# Carrier.net
KiCad netlist of a schematic drawn in Altium Designer
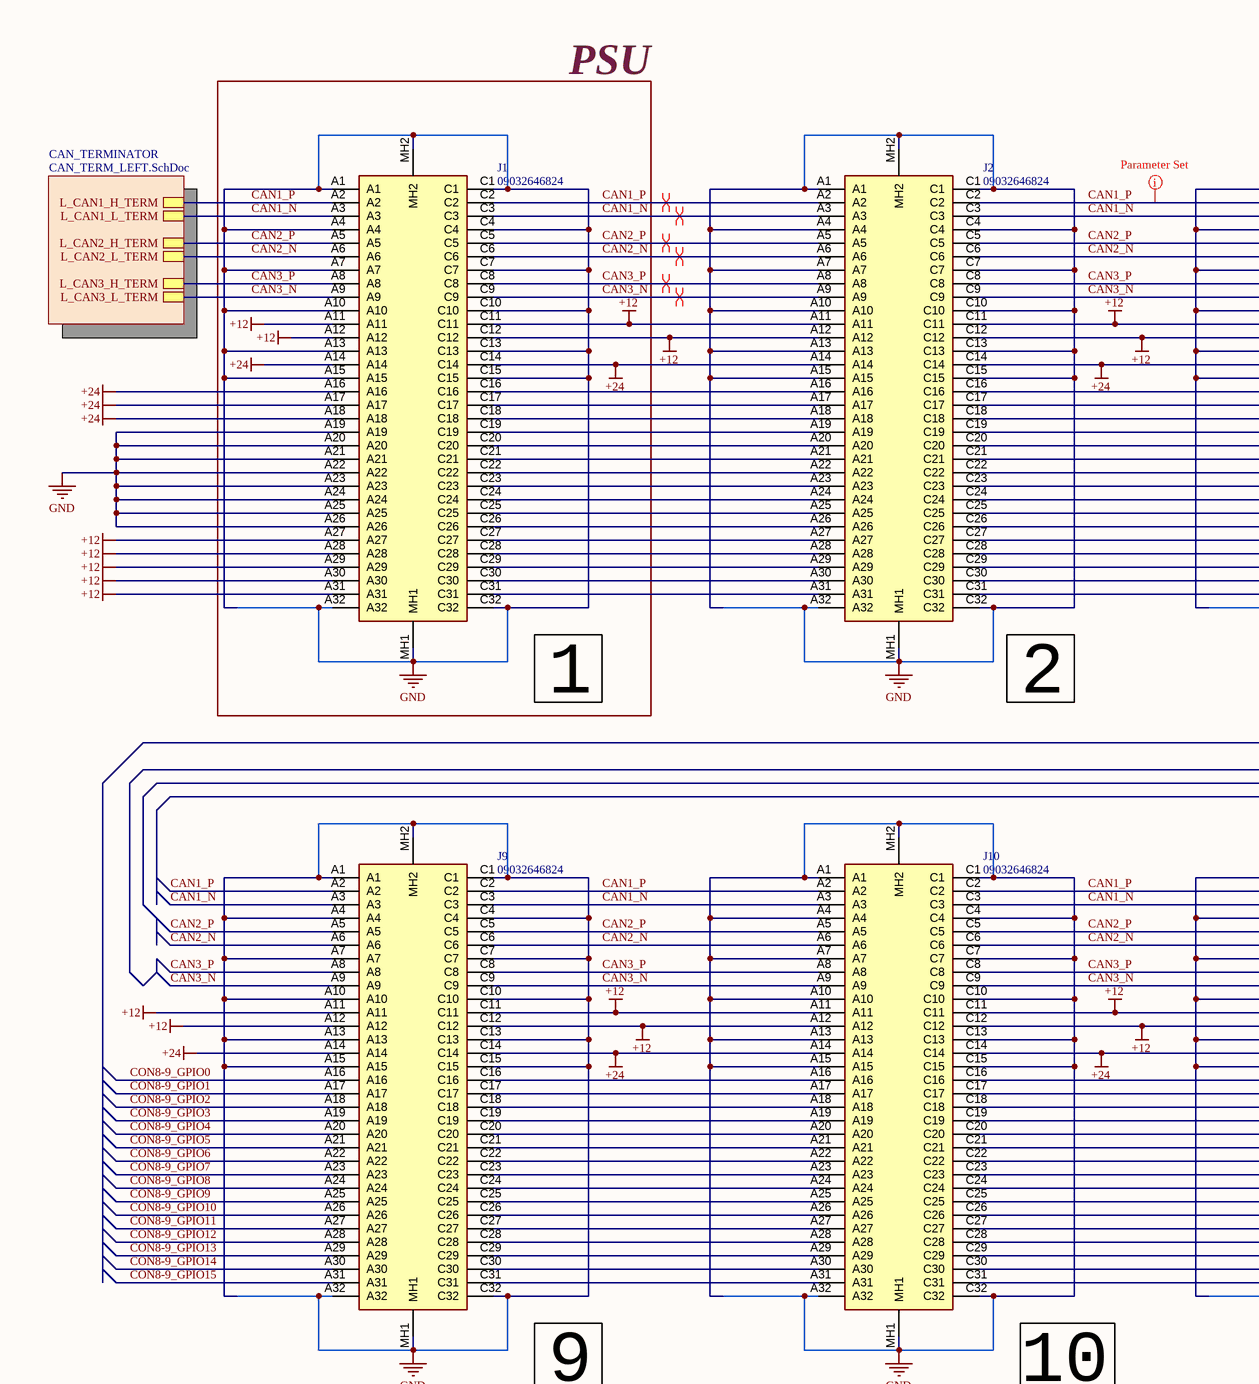
[diagram p0: Carrier.SchDoc, top left]
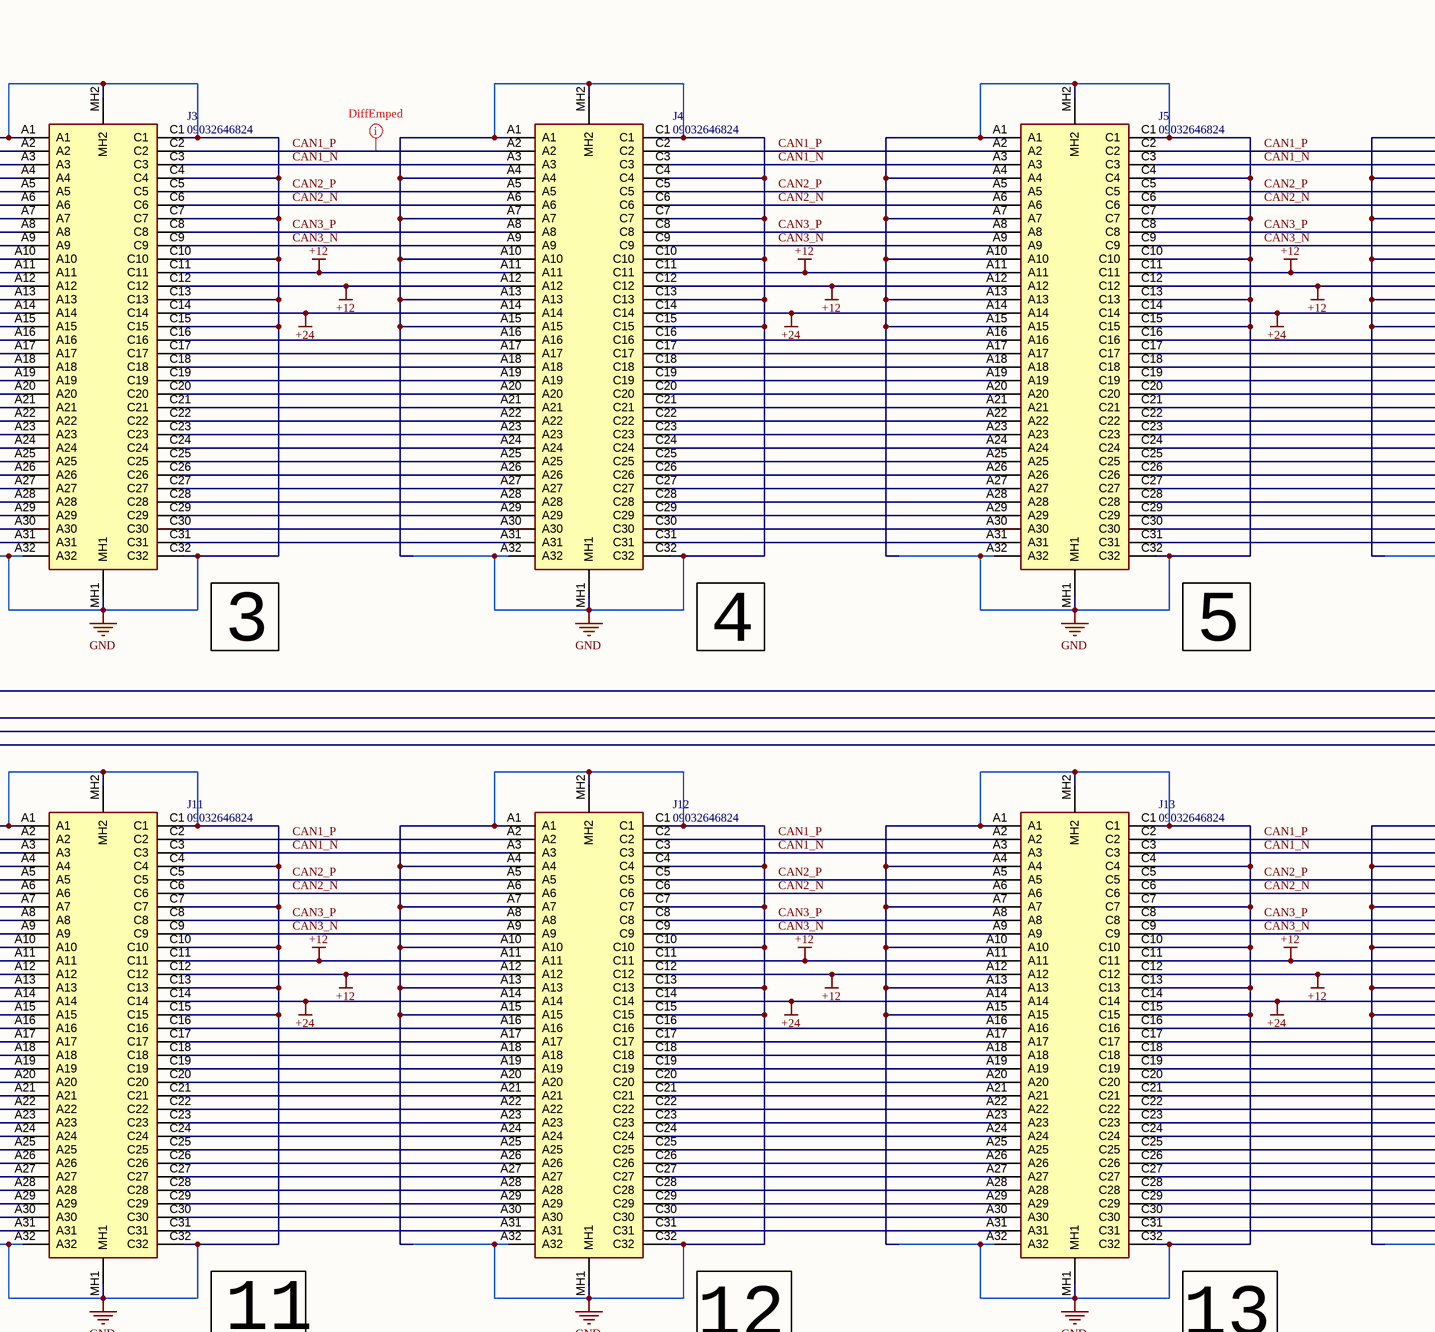
[diagram p1: Carrier.SchDoc, top middle]
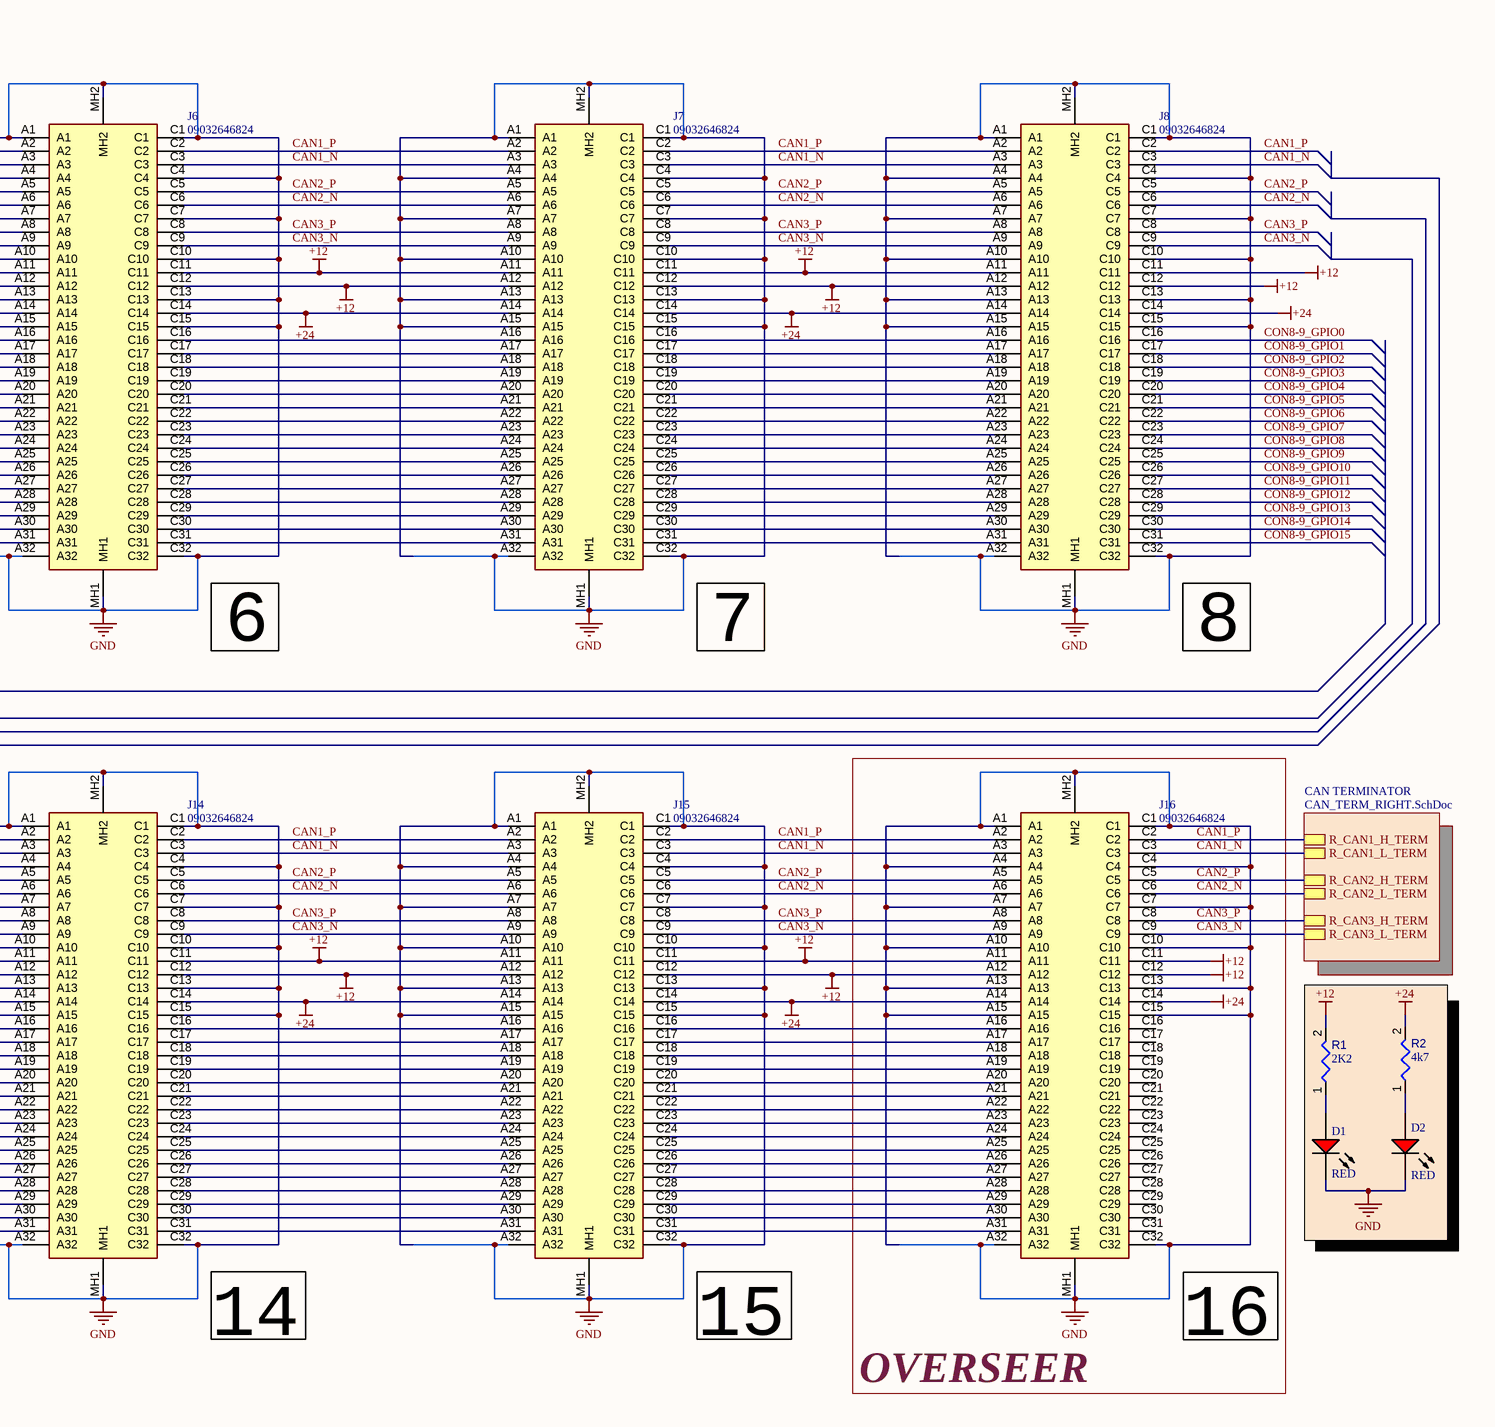
[diagram p2: Carrier.SchDoc, top right]
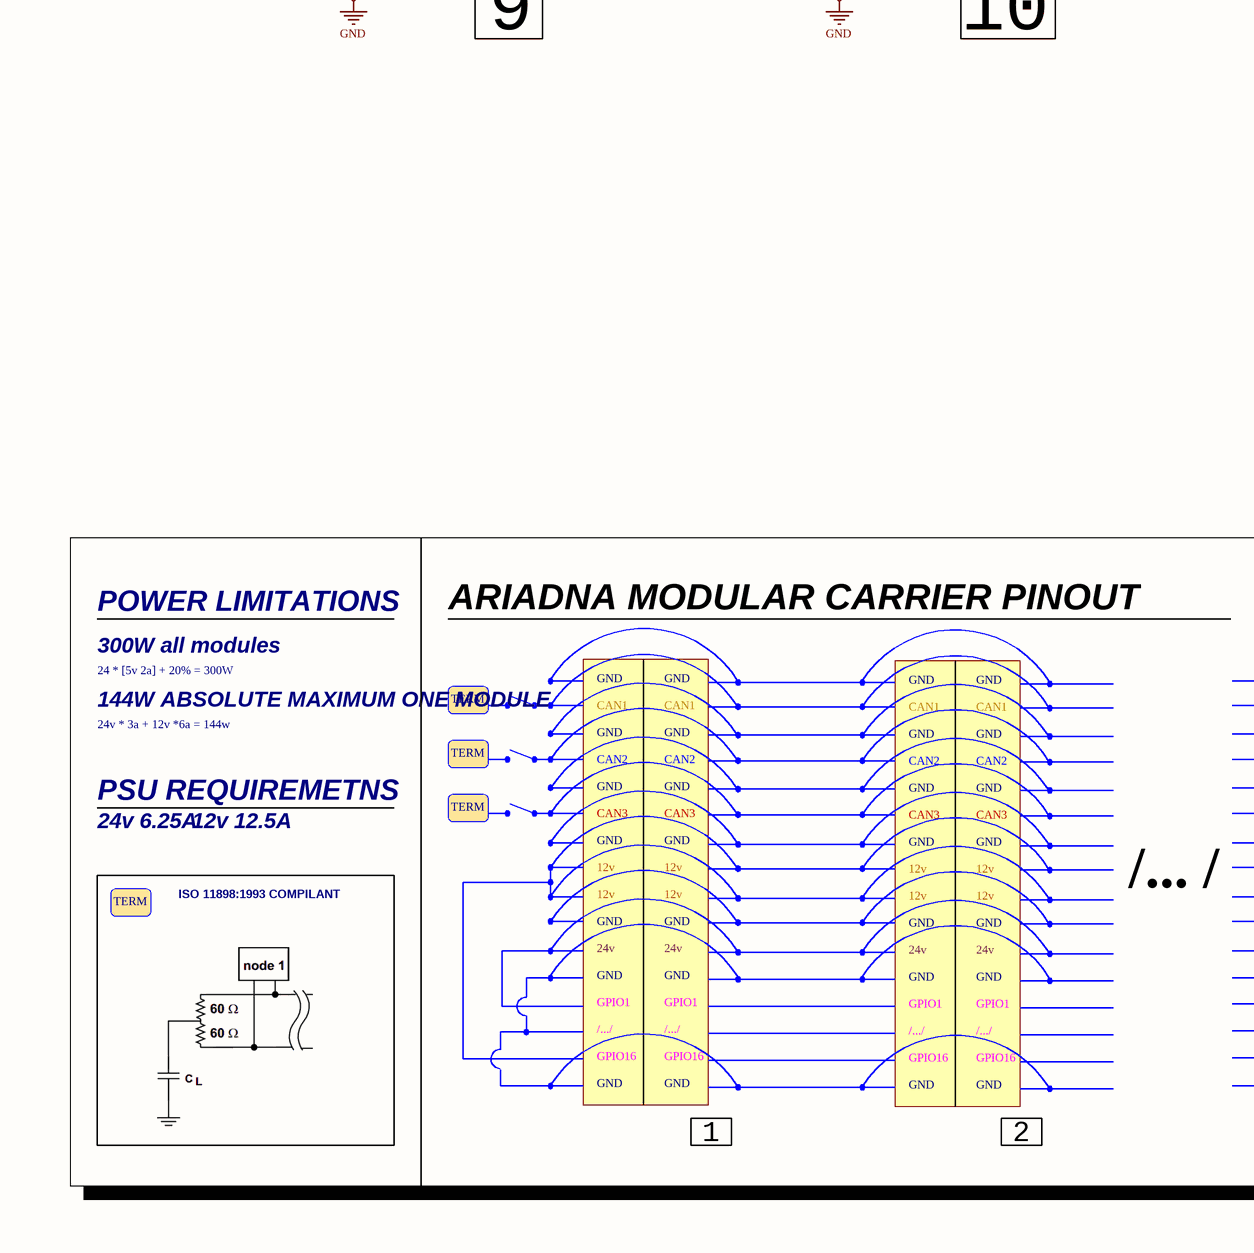
[diagram p3: Carrier.SchDoc, bottom left]
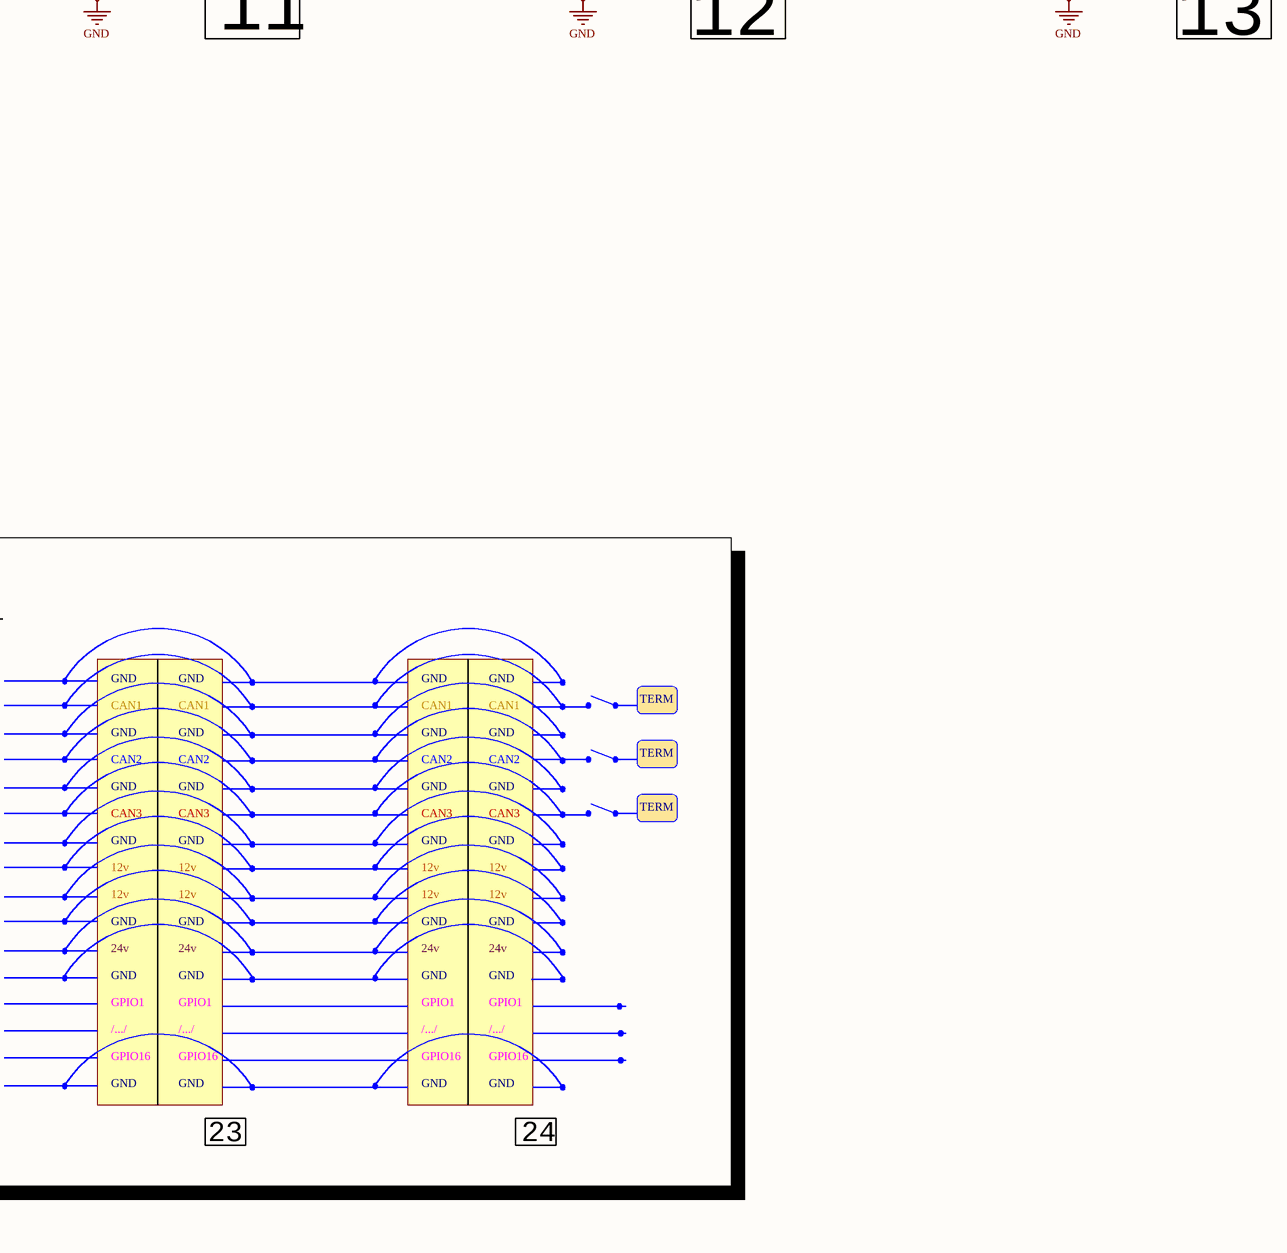
[diagram p4: Carrier.SchDoc, bottom middle]
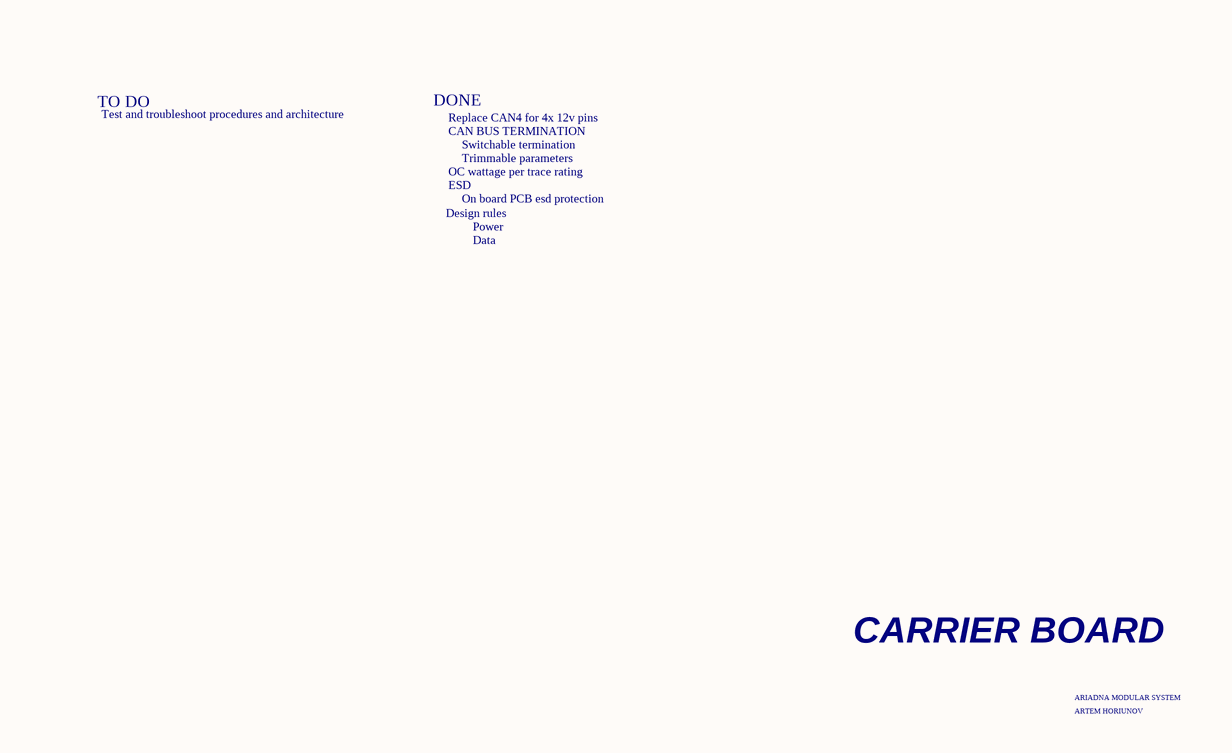
[diagram p5: Carrier.SchDoc, bottom right]

(export (version "E")
  (design (tool "Eeschema 10.0.6"))
  (components
    (comp (ref "D1")
      (value "RED")
      (footprint "AVAG-HSMX-C190_V")
      (description "LED Uni-Color Red, 65 mW, 20 mA, -40 to 85 degC, 2-Pin SMD, RoHS, Tape and Reel")
      (libsource (lib "Altium Content Vault") (part "LED-RED-AK-2"))
    )
    (comp (ref "D2")
      (value "RED")
      (footprint "AVAG-HSMX-C190_V")
      (description "LED Uni-Color Red, 65 mW, 20 mA, -40 to 85 degC, 2-Pin SMD, RoHS, Tape and Reel")
      (libsource (lib "Altium Content Vault") (part "LED-RED-AK-2"))
    )
    (comp (ref "J1")
      (value "09032646824")
      (footprint "09032646824")
      (description "DIN C female straight 64pin, 2.9mm tails, PL2 (rows a,c loaded)")
      (libsource (lib "09032646824") (part "09032646824"))
    )
    (comp (ref "J2")
      (value "09032646824")
      (footprint "09032646824")
      (description "DIN C female straight 64pin, 2.9mm tails, PL2 (rows a,c loaded)")
      (libsource (lib "09032646824") (part "09032646824"))
    )
    (comp (ref "J3")
      (value "09032646824")
      (footprint "09032646824")
      (description "DIN C female straight 64pin, 2.9mm tails, PL2 (rows a,c loaded)")
      (libsource (lib "09032646824") (part "09032646824"))
    )
    (comp (ref "J4")
      (value "09032646824")
      (footprint "09032646824")
      (description "DIN C female straight 64pin, 2.9mm tails, PL2 (rows a,c loaded)")
      (libsource (lib "09032646824") (part "09032646824"))
    )
    (comp (ref "J5")
      (value "09032646824")
      (footprint "09032646824")
      (description "DIN C female straight 64pin, 2.9mm tails, PL2 (rows a,c loaded)")
      (libsource (lib "09032646824") (part "09032646824"))
    )
    (comp (ref "J6")
      (value "09032646824")
      (footprint "09032646824")
      (description "DIN C female straight 64pin, 2.9mm tails, PL2 (rows a,c loaded)")
      (libsource (lib "09032646824") (part "09032646824"))
    )
    (comp (ref "J7")
      (value "09032646824")
      (footprint "09032646824")
      (description "DIN C female straight 64pin, 2.9mm tails, PL2 (rows a,c loaded)")
      (libsource (lib "09032646824") (part "09032646824"))
    )
    (comp (ref "J8")
      (value "09032646824")
      (footprint "09032646824")
      (description "DIN C female straight 64pin, 2.9mm tails, PL2 (rows a,c loaded)")
      (libsource (lib "09032646824") (part "09032646824"))
    )
    (comp (ref "J9")
      (value "09032646824")
      (footprint "09032646824")
      (description "DIN C female straight 64pin, 2.9mm tails, PL2 (rows a,c loaded)")
      (libsource (lib "09032646824") (part "09032646824"))
    )
    (comp (ref "J10")
      (value "09032646824")
      (footprint "09032646824")
      (description "DIN C female straight 64pin, 2.9mm tails, PL2 (rows a,c loaded)")
      (libsource (lib "09032646824") (part "09032646824"))
    )
    (comp (ref "J11")
      (value "09032646824")
      (footprint "09032646824")
      (description "DIN C female straight 64pin, 2.9mm tails, PL2 (rows a,c loaded)")
      (libsource (lib "09032646824") (part "09032646824"))
    )
    (comp (ref "J12")
      (value "09032646824")
      (footprint "09032646824")
      (description "DIN C female straight 64pin, 2.9mm tails, PL2 (rows a,c loaded)")
      (libsource (lib "09032646824") (part "09032646824"))
    )
    (comp (ref "J13")
      (value "09032646824")
      (footprint "09032646824")
      (description "DIN C female straight 64pin, 2.9mm tails, PL2 (rows a,c loaded)")
      (libsource (lib "09032646824") (part "09032646824"))
    )
    (comp (ref "J14")
      (value "09032646824")
      (footprint "09032646824")
      (description "DIN C female straight 64pin, 2.9mm tails, PL2 (rows a,c loaded)")
      (libsource (lib "09032646824") (part "09032646824"))
    )
    (comp (ref "J15")
      (value "09032646824")
      (footprint "09032646824")
      (description "DIN C female straight 64pin, 2.9mm tails, PL2 (rows a,c loaded)")
      (libsource (lib "09032646824") (part "09032646824"))
    )
    (comp (ref "J16")
      (value "09032646824")
      (footprint "09032646824")
      (description "DIN C female straight 64pin, 2.9mm tails, PL2 (rows a,c loaded)")
      (libsource (lib "09032646824") (part "09032646824"))
    )
    (comp (ref "R1")
      (value "2K2")
      (footprint "RESC0805(2012)_L")
      (description "4R7 0.125W 5% 0805 (2012 Metric)  SMD")
      (fields (field (name "POWER") "125mW") (field (name "TOLERANCE") "5%"))
      (libsource (lib "WUST") (part "4D7R5J"))
    )
    (comp (ref "R2")
      (value "4k7")
      (footprint "RESC0805(2012)_L")
      (description "4R7 0.125W 5% 0805 (2012 Metric)  SMD")
      (fields (field (name "POWER") "125mW") (field (name "TOLERANCE") "5%"))
      (libsource (lib "WUST") (part "4D7R5J"))
    )
  )
  (nets
    (net (code "1") (name "+12") (class "Default")
      (node (ref "J1") (pin "A11") (pinfunction "A11_A11") (pintype "passive"))
      (node (ref "J1") (pin "A12") (pinfunction "A12_A12") (pintype "passive"))
      (node (ref "J1") (pin "A27") (pinfunction "A27_A27") (pintype "passive"))
      (node (ref "J1") (pin "A28") (pinfunction "A28_A28") (pintype "passive"))
      (node (ref "J1") (pin "A29") (pinfunction "A29_A29") (pintype "passive"))
      (node (ref "J1") (pin "A30") (pinfunction "A30_A30") (pintype "passive"))
      (node (ref "J1") (pin "A31") (pinfunction "A31_A31") (pintype "passive"))
      (node (ref "J1") (pin "C11") (pinfunction "C11_C11") (pintype "passive"))
      (node (ref "J1") (pin "C12") (pinfunction "C12_C12") (pintype "passive"))
      (node (ref "J10") (pin "A11") (pinfunction "A11_A11") (pintype "passive"))
      (node (ref "J10") (pin "A12") (pinfunction "A12_A12") (pintype "passive"))
      (node (ref "J10") (pin "C11") (pinfunction "C11_C11") (pintype "passive"))
      (node (ref "J10") (pin "C12") (pinfunction "C12_C12") (pintype "passive"))
      (node (ref "J11") (pin "A11") (pinfunction "A11_A11") (pintype "passive"))
      (node (ref "J11") (pin "A12") (pinfunction "A12_A12") (pintype "passive"))
      (node (ref "J11") (pin "C11") (pinfunction "C11_C11") (pintype "passive"))
      (node (ref "J11") (pin "C12") (pinfunction "C12_C12") (pintype "passive"))
      (node (ref "J12") (pin "A11") (pinfunction "A11_A11") (pintype "passive"))
      (node (ref "J12") (pin "A12") (pinfunction "A12_A12") (pintype "passive"))
      (node (ref "J12") (pin "C11") (pinfunction "C11_C11") (pintype "passive"))
      (node (ref "J12") (pin "C12") (pinfunction "C12_C12") (pintype "passive"))
      (node (ref "J13") (pin "A11") (pinfunction "A11_A11") (pintype "passive"))
      (node (ref "J13") (pin "A12") (pinfunction "A12_A12") (pintype "passive"))
      (node (ref "J13") (pin "C11") (pinfunction "C11_C11") (pintype "passive"))
      (node (ref "J13") (pin "C12") (pinfunction "C12_C12") (pintype "passive"))
      (node (ref "J14") (pin "A11") (pinfunction "A11_A11") (pintype "passive"))
      (node (ref "J14") (pin "A12") (pinfunction "A12_A12") (pintype "passive"))
      (node (ref "J14") (pin "C11") (pinfunction "C11_C11") (pintype "passive"))
      (node (ref "J14") (pin "C12") (pinfunction "C12_C12") (pintype "passive"))
      (node (ref "J15") (pin "A11") (pinfunction "A11_A11") (pintype "passive"))
      (node (ref "J15") (pin "A12") (pinfunction "A12_A12") (pintype "passive"))
      (node (ref "J15") (pin "C11") (pinfunction "C11_C11") (pintype "passive"))
      (node (ref "J15") (pin "C12") (pinfunction "C12_C12") (pintype "passive"))
      (node (ref "J16") (pin "A11") (pinfunction "A11_A11") (pintype "passive"))
      (node (ref "J16") (pin "A12") (pinfunction "A12_A12") (pintype "passive"))
      (node (ref "J16") (pin "C11") (pinfunction "C11_C11") (pintype "passive"))
      (node (ref "J16") (pin "C12") (pinfunction "C12_C12") (pintype "passive"))
      (node (ref "J2") (pin "A11") (pinfunction "A11_A11") (pintype "passive"))
      (node (ref "J2") (pin "A12") (pinfunction "A12_A12") (pintype "passive"))
      (node (ref "J2") (pin "C11") (pinfunction "C11_C11") (pintype "passive"))
      (node (ref "J2") (pin "C12") (pinfunction "C12_C12") (pintype "passive"))
      (node (ref "J3") (pin "A11") (pinfunction "A11_A11") (pintype "passive"))
      (node (ref "J3") (pin "A12") (pinfunction "A12_A12") (pintype "passive"))
      (node (ref "J3") (pin "C11") (pinfunction "C11_C11") (pintype "passive"))
      (node (ref "J3") (pin "C12") (pinfunction "C12_C12") (pintype "passive"))
      (node (ref "J4") (pin "A11") (pinfunction "A11_A11") (pintype "passive"))
      (node (ref "J4") (pin "A12") (pinfunction "A12_A12") (pintype "passive"))
      (node (ref "J4") (pin "C11") (pinfunction "C11_C11") (pintype "passive"))
      (node (ref "J4") (pin "C12") (pinfunction "C12_C12") (pintype "passive"))
      (node (ref "J5") (pin "A11") (pinfunction "A11_A11") (pintype "passive"))
      (node (ref "J5") (pin "A12") (pinfunction "A12_A12") (pintype "passive"))
      (node (ref "J5") (pin "C11") (pinfunction "C11_C11") (pintype "passive"))
      (node (ref "J5") (pin "C12") (pinfunction "C12_C12") (pintype "passive"))
      (node (ref "J6") (pin "A11") (pinfunction "A11_A11") (pintype "passive"))
      (node (ref "J6") (pin "A12") (pinfunction "A12_A12") (pintype "passive"))
      (node (ref "J6") (pin "C11") (pinfunction "C11_C11") (pintype "passive"))
      (node (ref "J6") (pin "C12") (pinfunction "C12_C12") (pintype "passive"))
      (node (ref "J7") (pin "A11") (pinfunction "A11_A11") (pintype "passive"))
      (node (ref "J7") (pin "A12") (pinfunction "A12_A12") (pintype "passive"))
      (node (ref "J7") (pin "C11") (pinfunction "C11_C11") (pintype "passive"))
      (node (ref "J7") (pin "C12") (pinfunction "C12_C12") (pintype "passive"))
      (node (ref "J8") (pin "A11") (pinfunction "A11_A11") (pintype "passive"))
      (node (ref "J8") (pin "A12") (pinfunction "A12_A12") (pintype "passive"))
      (node (ref "J8") (pin "C11") (pinfunction "C11_C11") (pintype "passive"))
      (node (ref "J8") (pin "C12") (pinfunction "C12_C12") (pintype "passive"))
      (node (ref "J9") (pin "A11") (pinfunction "A11_A11") (pintype "passive"))
      (node (ref "J9") (pin "A12") (pinfunction "A12_A12") (pintype "passive"))
      (node (ref "J9") (pin "C11") (pinfunction "C11_C11") (pintype "passive"))
      (node (ref "J9") (pin "C12") (pinfunction "C12_C12") (pintype "passive"))
      (node (ref "R1") (pin "2") (pinfunction "2_2") (pintype "passive"))
    )
    (net (code "2") (name "+24") (class "Default")
      (node (ref "J1") (pin "A14") (pinfunction "A14_A14") (pintype "passive"))
      (node (ref "J1") (pin "A16") (pinfunction "A16_A16") (pintype "passive"))
      (node (ref "J1") (pin "A17") (pinfunction "A17_A17") (pintype "passive"))
      (node (ref "J1") (pin "A18") (pinfunction "A18_A18") (pintype "passive"))
      (node (ref "J1") (pin "C14") (pinfunction "C14_C14") (pintype "passive"))
      (node (ref "J10") (pin "A14") (pinfunction "A14_A14") (pintype "passive"))
      (node (ref "J10") (pin "C14") (pinfunction "C14_C14") (pintype "passive"))
      (node (ref "J11") (pin "A14") (pinfunction "A14_A14") (pintype "passive"))
      (node (ref "J11") (pin "C14") (pinfunction "C14_C14") (pintype "passive"))
      (node (ref "J12") (pin "A14") (pinfunction "A14_A14") (pintype "passive"))
      (node (ref "J12") (pin "C14") (pinfunction "C14_C14") (pintype "passive"))
      (node (ref "J13") (pin "A14") (pinfunction "A14_A14") (pintype "passive"))
      (node (ref "J13") (pin "C14") (pinfunction "C14_C14") (pintype "passive"))
      (node (ref "J14") (pin "A14") (pinfunction "A14_A14") (pintype "passive"))
      (node (ref "J14") (pin "C14") (pinfunction "C14_C14") (pintype "passive"))
      (node (ref "J15") (pin "A14") (pinfunction "A14_A14") (pintype "passive"))
      (node (ref "J15") (pin "C14") (pinfunction "C14_C14") (pintype "passive"))
      (node (ref "J16") (pin "A14") (pinfunction "A14_A14") (pintype "passive"))
      (node (ref "J16") (pin "C14") (pinfunction "C14_C14") (pintype "passive"))
      (node (ref "J2") (pin "A14") (pinfunction "A14_A14") (pintype "passive"))
      (node (ref "J2") (pin "C14") (pinfunction "C14_C14") (pintype "passive"))
      (node (ref "J3") (pin "A14") (pinfunction "A14_A14") (pintype "passive"))
      (node (ref "J3") (pin "C14") (pinfunction "C14_C14") (pintype "passive"))
      (node (ref "J4") (pin "A14") (pinfunction "A14_A14") (pintype "passive"))
      (node (ref "J4") (pin "C14") (pinfunction "C14_C14") (pintype "passive"))
      (node (ref "J5") (pin "A14") (pinfunction "A14_A14") (pintype "passive"))
      (node (ref "J5") (pin "C14") (pinfunction "C14_C14") (pintype "passive"))
      (node (ref "J6") (pin "A14") (pinfunction "A14_A14") (pintype "passive"))
      (node (ref "J6") (pin "C14") (pinfunction "C14_C14") (pintype "passive"))
      (node (ref "J7") (pin "A14") (pinfunction "A14_A14") (pintype "passive"))
      (node (ref "J7") (pin "C14") (pinfunction "C14_C14") (pintype "passive"))
      (node (ref "J8") (pin "A14") (pinfunction "A14_A14") (pintype "passive"))
      (node (ref "J8") (pin "C14") (pinfunction "C14_C14") (pintype "passive"))
      (node (ref "J9") (pin "A14") (pinfunction "A14_A14") (pintype "passive"))
      (node (ref "J9") (pin "C14") (pinfunction "C14_C14") (pintype "passive"))
      (node (ref "R2") (pin "2") (pinfunction "2_2") (pintype "passive"))
    )
    (net (code "3") (name "/CAN1_N") (class "Default")
      (node (ref "J1") (pin "A3") (pinfunction "A3_A3") (pintype "passive"))
      (node (ref "J1") (pin "C3") (pinfunction "C3_C3") (pintype "passive"))
      (node (ref "J10") (pin "A3") (pinfunction "A3_A3") (pintype "passive"))
      (node (ref "J10") (pin "C3") (pinfunction "C3_C3") (pintype "passive"))
      (node (ref "J11") (pin "A3") (pinfunction "A3_A3") (pintype "passive"))
      (node (ref "J11") (pin "C3") (pinfunction "C3_C3") (pintype "passive"))
      (node (ref "J12") (pin "A3") (pinfunction "A3_A3") (pintype "passive"))
      (node (ref "J12") (pin "C3") (pinfunction "C3_C3") (pintype "passive"))
      (node (ref "J13") (pin "A3") (pinfunction "A3_A3") (pintype "passive"))
      (node (ref "J13") (pin "C3") (pinfunction "C3_C3") (pintype "passive"))
      (node (ref "J14") (pin "A3") (pinfunction "A3_A3") (pintype "passive"))
      (node (ref "J14") (pin "C3") (pinfunction "C3_C3") (pintype "passive"))
      (node (ref "J15") (pin "A3") (pinfunction "A3_A3") (pintype "passive"))
      (node (ref "J15") (pin "C3") (pinfunction "C3_C3") (pintype "passive"))
      (node (ref "J16") (pin "A3") (pinfunction "A3_A3") (pintype "passive"))
      (node (ref "J16") (pin "C3") (pinfunction "C3_C3") (pintype "passive"))
      (node (ref "J2") (pin "A3") (pinfunction "A3_A3") (pintype "passive"))
      (node (ref "J2") (pin "C3") (pinfunction "C3_C3") (pintype "passive"))
      (node (ref "J3") (pin "A3") (pinfunction "A3_A3") (pintype "passive"))
      (node (ref "J3") (pin "C3") (pinfunction "C3_C3") (pintype "passive"))
      (node (ref "J4") (pin "A3") (pinfunction "A3_A3") (pintype "passive"))
      (node (ref "J4") (pin "C3") (pinfunction "C3_C3") (pintype "passive"))
      (node (ref "J5") (pin "A3") (pinfunction "A3_A3") (pintype "passive"))
      (node (ref "J5") (pin "C3") (pinfunction "C3_C3") (pintype "passive"))
      (node (ref "J6") (pin "A3") (pinfunction "A3_A3") (pintype "passive"))
      (node (ref "J6") (pin "C3") (pinfunction "C3_C3") (pintype "passive"))
      (node (ref "J7") (pin "A3") (pinfunction "A3_A3") (pintype "passive"))
      (node (ref "J7") (pin "C3") (pinfunction "C3_C3") (pintype "passive"))
      (node (ref "J8") (pin "A3") (pinfunction "A3_A3") (pintype "passive"))
      (node (ref "J8") (pin "C3") (pinfunction "C3_C3") (pintype "passive"))
      (node (ref "J9") (pin "A3") (pinfunction "A3_A3") (pintype "passive"))
      (node (ref "J9") (pin "C3") (pinfunction "C3_C3") (pintype "passive"))
    )
    (net (code "4") (name "/CAN1_P") (class "Default")
      (node (ref "J1") (pin "A2") (pinfunction "A2_A2") (pintype "passive"))
      (node (ref "J1") (pin "C2") (pinfunction "C2_C2") (pintype "passive"))
      (node (ref "J10") (pin "A2") (pinfunction "A2_A2") (pintype "passive"))
      (node (ref "J10") (pin "C2") (pinfunction "C2_C2") (pintype "passive"))
      (node (ref "J11") (pin "A2") (pinfunction "A2_A2") (pintype "passive"))
      (node (ref "J11") (pin "C2") (pinfunction "C2_C2") (pintype "passive"))
      (node (ref "J12") (pin "A2") (pinfunction "A2_A2") (pintype "passive"))
      (node (ref "J12") (pin "C2") (pinfunction "C2_C2") (pintype "passive"))
      (node (ref "J13") (pin "A2") (pinfunction "A2_A2") (pintype "passive"))
      (node (ref "J13") (pin "C2") (pinfunction "C2_C2") (pintype "passive"))
      (node (ref "J14") (pin "A2") (pinfunction "A2_A2") (pintype "passive"))
      (node (ref "J14") (pin "C2") (pinfunction "C2_C2") (pintype "passive"))
      (node (ref "J15") (pin "A2") (pinfunction "A2_A2") (pintype "passive"))
      (node (ref "J15") (pin "C2") (pinfunction "C2_C2") (pintype "passive"))
      (node (ref "J16") (pin "A2") (pinfunction "A2_A2") (pintype "passive"))
      (node (ref "J16") (pin "C2") (pinfunction "C2_C2") (pintype "passive"))
      (node (ref "J2") (pin "A2") (pinfunction "A2_A2") (pintype "passive"))
      (node (ref "J2") (pin "C2") (pinfunction "C2_C2") (pintype "passive"))
      (node (ref "J3") (pin "A2") (pinfunction "A2_A2") (pintype "passive"))
      (node (ref "J3") (pin "C2") (pinfunction "C2_C2") (pintype "passive"))
      (node (ref "J4") (pin "A2") (pinfunction "A2_A2") (pintype "passive"))
      (node (ref "J4") (pin "C2") (pinfunction "C2_C2") (pintype "passive"))
      (node (ref "J5") (pin "A2") (pinfunction "A2_A2") (pintype "passive"))
      (node (ref "J5") (pin "C2") (pinfunction "C2_C2") (pintype "passive"))
      (node (ref "J6") (pin "A2") (pinfunction "A2_A2") (pintype "passive"))
      (node (ref "J6") (pin "C2") (pinfunction "C2_C2") (pintype "passive"))
      (node (ref "J7") (pin "A2") (pinfunction "A2_A2") (pintype "passive"))
      (node (ref "J7") (pin "C2") (pinfunction "C2_C2") (pintype "passive"))
      (node (ref "J8") (pin "A2") (pinfunction "A2_A2") (pintype "passive"))
      (node (ref "J8") (pin "C2") (pinfunction "C2_C2") (pintype "passive"))
      (node (ref "J9") (pin "A2") (pinfunction "A2_A2") (pintype "passive"))
      (node (ref "J9") (pin "C2") (pinfunction "C2_C2") (pintype "passive"))
    )
    (net (code "5") (name "/CAN2_N") (class "Default")
      (node (ref "J1") (pin "A6") (pinfunction "A6_A6") (pintype "passive"))
      (node (ref "J1") (pin "C6") (pinfunction "C6_C6") (pintype "passive"))
      (node (ref "J10") (pin "A6") (pinfunction "A6_A6") (pintype "passive"))
      (node (ref "J10") (pin "C6") (pinfunction "C6_C6") (pintype "passive"))
      (node (ref "J11") (pin "A6") (pinfunction "A6_A6") (pintype "passive"))
      (node (ref "J11") (pin "C6") (pinfunction "C6_C6") (pintype "passive"))
      (node (ref "J12") (pin "A6") (pinfunction "A6_A6") (pintype "passive"))
      (node (ref "J12") (pin "C6") (pinfunction "C6_C6") (pintype "passive"))
      (node (ref "J13") (pin "A6") (pinfunction "A6_A6") (pintype "passive"))
      (node (ref "J13") (pin "C6") (pinfunction "C6_C6") (pintype "passive"))
      (node (ref "J14") (pin "A6") (pinfunction "A6_A6") (pintype "passive"))
      (node (ref "J14") (pin "C6") (pinfunction "C6_C6") (pintype "passive"))
      (node (ref "J15") (pin "A6") (pinfunction "A6_A6") (pintype "passive"))
      (node (ref "J15") (pin "C6") (pinfunction "C6_C6") (pintype "passive"))
      (node (ref "J16") (pin "A6") (pinfunction "A6_A6") (pintype "passive"))
      (node (ref "J16") (pin "C6") (pinfunction "C6_C6") (pintype "passive"))
      (node (ref "J2") (pin "A6") (pinfunction "A6_A6") (pintype "passive"))
      (node (ref "J2") (pin "C6") (pinfunction "C6_C6") (pintype "passive"))
      (node (ref "J3") (pin "A6") (pinfunction "A6_A6") (pintype "passive"))
      (node (ref "J3") (pin "C6") (pinfunction "C6_C6") (pintype "passive"))
      (node (ref "J4") (pin "A6") (pinfunction "A6_A6") (pintype "passive"))
      (node (ref "J4") (pin "C6") (pinfunction "C6_C6") (pintype "passive"))
      (node (ref "J5") (pin "A6") (pinfunction "A6_A6") (pintype "passive"))
      (node (ref "J5") (pin "C6") (pinfunction "C6_C6") (pintype "passive"))
      (node (ref "J6") (pin "A6") (pinfunction "A6_A6") (pintype "passive"))
      (node (ref "J6") (pin "C6") (pinfunction "C6_C6") (pintype "passive"))
      (node (ref "J7") (pin "A6") (pinfunction "A6_A6") (pintype "passive"))
      (node (ref "J7") (pin "C6") (pinfunction "C6_C6") (pintype "passive"))
      (node (ref "J8") (pin "A6") (pinfunction "A6_A6") (pintype "passive"))
      (node (ref "J8") (pin "C6") (pinfunction "C6_C6") (pintype "passive"))
      (node (ref "J9") (pin "A6") (pinfunction "A6_A6") (pintype "passive"))
      (node (ref "J9") (pin "C6") (pinfunction "C6_C6") (pintype "passive"))
    )
    (net (code "6") (name "/CAN2_P") (class "Default")
      (node (ref "J1") (pin "A5") (pinfunction "A5_A5") (pintype "passive"))
      (node (ref "J1") (pin "C5") (pinfunction "C5_C5") (pintype "passive"))
      (node (ref "J10") (pin "A5") (pinfunction "A5_A5") (pintype "passive"))
      (node (ref "J10") (pin "C5") (pinfunction "C5_C5") (pintype "passive"))
      (node (ref "J11") (pin "A5") (pinfunction "A5_A5") (pintype "passive"))
      (node (ref "J11") (pin "C5") (pinfunction "C5_C5") (pintype "passive"))
      (node (ref "J12") (pin "A5") (pinfunction "A5_A5") (pintype "passive"))
      (node (ref "J12") (pin "C5") (pinfunction "C5_C5") (pintype "passive"))
      (node (ref "J13") (pin "A5") (pinfunction "A5_A5") (pintype "passive"))
      (node (ref "J13") (pin "C5") (pinfunction "C5_C5") (pintype "passive"))
      (node (ref "J14") (pin "A5") (pinfunction "A5_A5") (pintype "passive"))
      (node (ref "J14") (pin "C5") (pinfunction "C5_C5") (pintype "passive"))
      (node (ref "J15") (pin "A5") (pinfunction "A5_A5") (pintype "passive"))
      (node (ref "J15") (pin "C5") (pinfunction "C5_C5") (pintype "passive"))
      (node (ref "J16") (pin "A5") (pinfunction "A5_A5") (pintype "passive"))
      (node (ref "J16") (pin "C5") (pinfunction "C5_C5") (pintype "passive"))
      (node (ref "J2") (pin "A5") (pinfunction "A5_A5") (pintype "passive"))
      (node (ref "J2") (pin "C5") (pinfunction "C5_C5") (pintype "passive"))
      (node (ref "J3") (pin "A5") (pinfunction "A5_A5") (pintype "passive"))
      (node (ref "J3") (pin "C5") (pinfunction "C5_C5") (pintype "passive"))
      (node (ref "J4") (pin "A5") (pinfunction "A5_A5") (pintype "passive"))
      (node (ref "J4") (pin "C5") (pinfunction "C5_C5") (pintype "passive"))
      (node (ref "J5") (pin "A5") (pinfunction "A5_A5") (pintype "passive"))
      (node (ref "J5") (pin "C5") (pinfunction "C5_C5") (pintype "passive"))
      (node (ref "J6") (pin "A5") (pinfunction "A5_A5") (pintype "passive"))
      (node (ref "J6") (pin "C5") (pinfunction "C5_C5") (pintype "passive"))
      (node (ref "J7") (pin "A5") (pinfunction "A5_A5") (pintype "passive"))
      (node (ref "J7") (pin "C5") (pinfunction "C5_C5") (pintype "passive"))
      (node (ref "J8") (pin "A5") (pinfunction "A5_A5") (pintype "passive"))
      (node (ref "J8") (pin "C5") (pinfunction "C5_C5") (pintype "passive"))
      (node (ref "J9") (pin "A5") (pinfunction "A5_A5") (pintype "passive"))
      (node (ref "J9") (pin "C5") (pinfunction "C5_C5") (pintype "passive"))
    )
    (net (code "7") (name "/CAN3_N") (class "Default")
      (node (ref "J1") (pin "A9") (pinfunction "A9_A9") (pintype "passive"))
      (node (ref "J1") (pin "C9") (pinfunction "C9_C9") (pintype "passive"))
      (node (ref "J10") (pin "A9") (pinfunction "A9_A9") (pintype "passive"))
      (node (ref "J10") (pin "C9") (pinfunction "C9_C9") (pintype "passive"))
      (node (ref "J11") (pin "A9") (pinfunction "A9_A9") (pintype "passive"))
      (node (ref "J11") (pin "C9") (pinfunction "C9_C9") (pintype "passive"))
      (node (ref "J12") (pin "A9") (pinfunction "A9_A9") (pintype "passive"))
      (node (ref "J12") (pin "C9") (pinfunction "C9_C9") (pintype "passive"))
      (node (ref "J13") (pin "A9") (pinfunction "A9_A9") (pintype "passive"))
      (node (ref "J13") (pin "C9") (pinfunction "C9_C9") (pintype "passive"))
      (node (ref "J14") (pin "A9") (pinfunction "A9_A9") (pintype "passive"))
      (node (ref "J14") (pin "C9") (pinfunction "C9_C9") (pintype "passive"))
      (node (ref "J15") (pin "A9") (pinfunction "A9_A9") (pintype "passive"))
      (node (ref "J15") (pin "C9") (pinfunction "C9_C9") (pintype "passive"))
      (node (ref "J16") (pin "A9") (pinfunction "A9_A9") (pintype "passive"))
      (node (ref "J16") (pin "C9") (pinfunction "C9_C9") (pintype "passive"))
      (node (ref "J2") (pin "A9") (pinfunction "A9_A9") (pintype "passive"))
      (node (ref "J2") (pin "C9") (pinfunction "C9_C9") (pintype "passive"))
      (node (ref "J3") (pin "A9") (pinfunction "A9_A9") (pintype "passive"))
      (node (ref "J3") (pin "C9") (pinfunction "C9_C9") (pintype "passive"))
      (node (ref "J4") (pin "A9") (pinfunction "A9_A9") (pintype "passive"))
      (node (ref "J4") (pin "C9") (pinfunction "C9_C9") (pintype "passive"))
      (node (ref "J5") (pin "A9") (pinfunction "A9_A9") (pintype "passive"))
      (node (ref "J5") (pin "C9") (pinfunction "C9_C9") (pintype "passive"))
      (node (ref "J6") (pin "A9") (pinfunction "A9_A9") (pintype "passive"))
      (node (ref "J6") (pin "C9") (pinfunction "C9_C9") (pintype "passive"))
      (node (ref "J7") (pin "A9") (pinfunction "A9_A9") (pintype "passive"))
      (node (ref "J7") (pin "C9") (pinfunction "C9_C9") (pintype "passive"))
      (node (ref "J8") (pin "A9") (pinfunction "A9_A9") (pintype "passive"))
      (node (ref "J8") (pin "C9") (pinfunction "C9_C9") (pintype "passive"))
      (node (ref "J9") (pin "A9") (pinfunction "A9_A9") (pintype "passive"))
      (node (ref "J9") (pin "C9") (pinfunction "C9_C9") (pintype "passive"))
    )
    (net (code "8") (name "/CAN3_P") (class "Default")
      (node (ref "J1") (pin "A8") (pinfunction "A8_A8") (pintype "passive"))
      (node (ref "J1") (pin "C8") (pinfunction "C8_C8") (pintype "passive"))
      (node (ref "J10") (pin "A8") (pinfunction "A8_A8") (pintype "passive"))
      (node (ref "J10") (pin "C8") (pinfunction "C8_C8") (pintype "passive"))
      (node (ref "J11") (pin "A8") (pinfunction "A8_A8") (pintype "passive"))
      (node (ref "J11") (pin "C8") (pinfunction "C8_C8") (pintype "passive"))
      (node (ref "J12") (pin "A8") (pinfunction "A8_A8") (pintype "passive"))
      (node (ref "J12") (pin "C8") (pinfunction "C8_C8") (pintype "passive"))
      (node (ref "J13") (pin "A8") (pinfunction "A8_A8") (pintype "passive"))
      (node (ref "J13") (pin "C8") (pinfunction "C8_C8") (pintype "passive"))
      (node (ref "J14") (pin "A8") (pinfunction "A8_A8") (pintype "passive"))
      (node (ref "J14") (pin "C8") (pinfunction "C8_C8") (pintype "passive"))
      (node (ref "J15") (pin "A8") (pinfunction "A8_A8") (pintype "passive"))
      (node (ref "J15") (pin "C8") (pinfunction "C8_C8") (pintype "passive"))
      (node (ref "J16") (pin "A8") (pinfunction "A8_A8") (pintype "passive"))
      (node (ref "J16") (pin "C8") (pinfunction "C8_C8") (pintype "passive"))
      (node (ref "J2") (pin "A8") (pinfunction "A8_A8") (pintype "passive"))
      (node (ref "J2") (pin "C8") (pinfunction "C8_C8") (pintype "passive"))
      (node (ref "J3") (pin "A8") (pinfunction "A8_A8") (pintype "passive"))
      (node (ref "J3") (pin "C8") (pinfunction "C8_C8") (pintype "passive"))
      (node (ref "J4") (pin "A8") (pinfunction "A8_A8") (pintype "passive"))
      (node (ref "J4") (pin "C8") (pinfunction "C8_C8") (pintype "passive"))
      (node (ref "J5") (pin "A8") (pinfunction "A8_A8") (pintype "passive"))
      (node (ref "J5") (pin "C8") (pinfunction "C8_C8") (pintype "passive"))
      (node (ref "J6") (pin "A8") (pinfunction "A8_A8") (pintype "passive"))
      (node (ref "J6") (pin "C8") (pinfunction "C8_C8") (pintype "passive"))
      (node (ref "J7") (pin "A8") (pinfunction "A8_A8") (pintype "passive"))
      (node (ref "J7") (pin "C8") (pinfunction "C8_C8") (pintype "passive"))
      (node (ref "J8") (pin "A8") (pinfunction "A8_A8") (pintype "passive"))
      (node (ref "J8") (pin "C8") (pinfunction "C8_C8") (pintype "passive"))
      (node (ref "J9") (pin "A8") (pinfunction "A8_A8") (pintype "passive"))
      (node (ref "J9") (pin "C8") (pinfunction "C8_C8") (pintype "passive"))
    )
    (net (code "9") (name "/CON8-9_GPIO0") (class "Default")
      (node (ref "J8") (pin "C16") (pinfunction "C16_C16") (pintype "passive"))
      (node (ref "J9") (pin "A16") (pinfunction "A16_A16") (pintype "passive"))
    )
    (net (code "10") (name "/CON8-9_GPIO1") (class "Default")
      (node (ref "J8") (pin "C17") (pinfunction "C17_C17") (pintype "passive"))
      (node (ref "J9") (pin "A17") (pinfunction "A17_A17") (pintype "passive"))
    )
    (net (code "11") (name "/CON8-9_GPIO2") (class "Default")
      (node (ref "J8") (pin "C18") (pinfunction "C18_C18") (pintype "passive"))
      (node (ref "J9") (pin "A18") (pinfunction "A18_A18") (pintype "passive"))
    )
    (net (code "12") (name "/CON8-9_GPIO3") (class "Default")
      (node (ref "J8") (pin "C19") (pinfunction "C19_C19") (pintype "passive"))
      (node (ref "J9") (pin "A19") (pinfunction "A19_A19") (pintype "passive"))
    )
    (net (code "13") (name "/CON8-9_GPIO4") (class "Default")
      (node (ref "J8") (pin "C20") (pinfunction "C20_C20") (pintype "passive"))
      (node (ref "J9") (pin "A20") (pinfunction "A20_A20") (pintype "passive"))
    )
    (net (code "14") (name "/CON8-9_GPIO5") (class "Default")
      (node (ref "J8") (pin "C21") (pinfunction "C21_C21") (pintype "passive"))
      (node (ref "J9") (pin "A21") (pinfunction "A21_A21") (pintype "passive"))
    )
    (net (code "15") (name "/CON8-9_GPIO6") (class "Default")
      (node (ref "J8") (pin "C22") (pinfunction "C22_C22") (pintype "passive"))
      (node (ref "J9") (pin "A22") (pinfunction "A22_A22") (pintype "passive"))
    )
    (net (code "16") (name "/CON8-9_GPIO7") (class "Default")
      (node (ref "J8") (pin "C23") (pinfunction "C23_C23") (pintype "passive"))
      (node (ref "J9") (pin "A23") (pinfunction "A23_A23") (pintype "passive"))
    )
    (net (code "17") (name "/CON8-9_GPIO8") (class "Default")
      (node (ref "J8") (pin "C24") (pinfunction "C24_C24") (pintype "passive"))
      (node (ref "J9") (pin "A24") (pinfunction "A24_A24") (pintype "passive"))
    )
    (net (code "18") (name "/CON8-9_GPIO9") (class "Default")
      (node (ref "J8") (pin "C25") (pinfunction "C25_C25") (pintype "passive"))
      (node (ref "J9") (pin "A25") (pinfunction "A25_A25") (pintype "passive"))
    )
    (net (code "19") (name "/CON8-9_GPIO10") (class "Default")
      (node (ref "J8") (pin "C26") (pinfunction "C26_C26") (pintype "passive"))
      (node (ref "J9") (pin "A26") (pinfunction "A26_A26") (pintype "passive"))
    )
    (net (code "20") (name "/CON8-9_GPIO11") (class "Default")
      (node (ref "J8") (pin "C27") (pinfunction "C27_C27") (pintype "passive"))
      (node (ref "J9") (pin "A27") (pinfunction "A27_A27") (pintype "passive"))
    )
    (net (code "21") (name "/CON8-9_GPIO12") (class "Default")
      (node (ref "J8") (pin "C28") (pinfunction "C28_C28") (pintype "passive"))
      (node (ref "J9") (pin "A28") (pinfunction "A28_A28") (pintype "passive"))
    )
    (net (code "22") (name "/CON8-9_GPIO13") (class "Default")
      (node (ref "J8") (pin "C29") (pinfunction "C29_C29") (pintype "passive"))
      (node (ref "J9") (pin "A29") (pinfunction "A29_A29") (pintype "passive"))
    )
    (net (code "23") (name "/CON8-9_GPIO14") (class "Default")
      (node (ref "J8") (pin "C30") (pinfunction "C30_C30") (pintype "passive"))
      (node (ref "J9") (pin "A30") (pinfunction "A30_A30") (pintype "passive"))
    )
    (net (code "24") (name "/CON8-9_GPIO15") (class "Default")
      (node (ref "J8") (pin "C31") (pinfunction "C31_C31") (pintype "passive"))
      (node (ref "J9") (pin "A31") (pinfunction "A31_A31") (pintype "passive"))
    )
    (net (code "25") (name "GND") (class "Default")
      (node (ref "D1") (pin "2") (pinfunction "K_2") (pintype "passive"))
      (node (ref "D2") (pin "2") (pinfunction "K_2") (pintype "passive"))
      (node (ref "J1") (pin "A1") (pinfunction "A1_A1") (pintype "passive"))
      (node (ref "J1") (pin "A10") (pinfunction "A10_A10") (pintype "passive"))
      (node (ref "J1") (pin "A13") (pinfunction "A13_A13") (pintype "passive"))
      (node (ref "J1") (pin "A15") (pinfunction "A15_A15") (pintype "passive"))
      (node (ref "J1") (pin "A19") (pinfunction "A19_A19") (pintype "passive"))
      (node (ref "J1") (pin "A20") (pinfunction "A20_A20") (pintype "passive"))
      (node (ref "J1") (pin "A21") (pinfunction "A21_A21") (pintype "passive"))
      (node (ref "J1") (pin "A22") (pinfunction "A22_A22") (pintype "passive"))
      (node (ref "J1") (pin "A23") (pinfunction "A23_A23") (pintype "passive"))
      (node (ref "J1") (pin "A24") (pinfunction "A24_A24") (pintype "passive"))
      (node (ref "J1") (pin "A25") (pinfunction "A25_A25") (pintype "passive"))
      (node (ref "J1") (pin "A26") (pinfunction "A26_A26") (pintype "passive"))
      (node (ref "J1") (pin "A32") (pinfunction "A32_A32") (pintype "passive"))
      (node (ref "J1") (pin "A4") (pinfunction "A4_A4") (pintype "passive"))
      (node (ref "J1") (pin "A7") (pinfunction "A7_A7") (pintype "passive"))
      (node (ref "J1") (pin "C1") (pinfunction "C1_C1") (pintype "passive"))
      (node (ref "J1") (pin "C10") (pinfunction "C10_C10") (pintype "passive"))
      (node (ref "J1") (pin "C13") (pinfunction "C13_C13") (pintype "passive"))
      (node (ref "J1") (pin "C15") (pinfunction "C15_C15") (pintype "passive"))
      (node (ref "J1") (pin "C32") (pinfunction "C32_C32") (pintype "passive"))
      (node (ref "J1") (pin "C4") (pinfunction "C4_C4") (pintype "passive"))
      (node (ref "J1") (pin "C7") (pinfunction "C7_C7") (pintype "passive"))
      (node (ref "J1") (pin "MH1") (pinfunction "MH1_MH1") (pintype "passive"))
      (node (ref "J1") (pin "MH2") (pinfunction "MH2_MH2") (pintype "passive"))
      (node (ref "J10") (pin "A1") (pinfunction "A1_A1") (pintype "passive"))
      (node (ref "J10") (pin "A10") (pinfunction "A10_A10") (pintype "passive"))
      (node (ref "J10") (pin "A13") (pinfunction "A13_A13") (pintype "passive"))
      (node (ref "J10") (pin "A15") (pinfunction "A15_A15") (pintype "passive"))
      (node (ref "J10") (pin "A32") (pinfunction "A32_A32") (pintype "passive"))
      (node (ref "J10") (pin "A4") (pinfunction "A4_A4") (pintype "passive"))
      (node (ref "J10") (pin "A7") (pinfunction "A7_A7") (pintype "passive"))
      (node (ref "J10") (pin "C1") (pinfunction "C1_C1") (pintype "passive"))
      (node (ref "J10") (pin "C10") (pinfunction "C10_C10") (pintype "passive"))
      (node (ref "J10") (pin "C13") (pinfunction "C13_C13") (pintype "passive"))
      (node (ref "J10") (pin "C15") (pinfunction "C15_C15") (pintype "passive"))
      (node (ref "J10") (pin "C32") (pinfunction "C32_C32") (pintype "passive"))
      (node (ref "J10") (pin "C4") (pinfunction "C4_C4") (pintype "passive"))
      (node (ref "J10") (pin "C7") (pinfunction "C7_C7") (pintype "passive"))
      (node (ref "J10") (pin "MH1") (pinfunction "MH1_MH1") (pintype "passive"))
      (node (ref "J10") (pin "MH2") (pinfunction "MH2_MH2") (pintype "passive"))
      (node (ref "J11") (pin "A1") (pinfunction "A1_A1") (pintype "passive"))
      (node (ref "J11") (pin "A10") (pinfunction "A10_A10") (pintype "passive"))
      (node (ref "J11") (pin "A13") (pinfunction "A13_A13") (pintype "passive"))
      (node (ref "J11") (pin "A15") (pinfunction "A15_A15") (pintype "passive"))
      (node (ref "J11") (pin "A32") (pinfunction "A32_A32") (pintype "passive"))
      (node (ref "J11") (pin "A4") (pinfunction "A4_A4") (pintype "passive"))
      (node (ref "J11") (pin "A7") (pinfunction "A7_A7") (pintype "passive"))
      (node (ref "J11") (pin "C1") (pinfunction "C1_C1") (pintype "passive"))
      (node (ref "J11") (pin "C10") (pinfunction "C10_C10") (pintype "passive"))
      (node (ref "J11") (pin "C13") (pinfunction "C13_C13") (pintype "passive"))
      (node (ref "J11") (pin "C15") (pinfunction "C15_C15") (pintype "passive"))
      (node (ref "J11") (pin "C32") (pinfunction "C32_C32") (pintype "passive"))
      (node (ref "J11") (pin "C4") (pinfunction "C4_C4") (pintype "passive"))
      (node (ref "J11") (pin "C7") (pinfunction "C7_C7") (pintype "passive"))
      (node (ref "J11") (pin "MH1") (pinfunction "MH1_MH1") (pintype "passive"))
      (node (ref "J11") (pin "MH2") (pinfunction "MH2_MH2") (pintype "passive"))
      (node (ref "J12") (pin "A1") (pinfunction "A1_A1") (pintype "passive"))
      (node (ref "J12") (pin "A10") (pinfunction "A10_A10") (pintype "passive"))
      (node (ref "J12") (pin "A13") (pinfunction "A13_A13") (pintype "passive"))
      (node (ref "J12") (pin "A15") (pinfunction "A15_A15") (pintype "passive"))
      (node (ref "J12") (pin "A32") (pinfunction "A32_A32") (pintype "passive"))
      (node (ref "J12") (pin "A4") (pinfunction "A4_A4") (pintype "passive"))
      (node (ref "J12") (pin "A7") (pinfunction "A7_A7") (pintype "passive"))
      (node (ref "J12") (pin "C1") (pinfunction "C1_C1") (pintype "passive"))
      (node (ref "J12") (pin "C10") (pinfunction "C10_C10") (pintype "passive"))
      (node (ref "J12") (pin "C13") (pinfunction "C13_C13") (pintype "passive"))
      (node (ref "J12") (pin "C15") (pinfunction "C15_C15") (pintype "passive"))
      (node (ref "J12") (pin "C32") (pinfunction "C32_C32") (pintype "passive"))
      (node (ref "J12") (pin "C4") (pinfunction "C4_C4") (pintype "passive"))
      (node (ref "J12") (pin "C7") (pinfunction "C7_C7") (pintype "passive"))
      (node (ref "J12") (pin "MH1") (pinfunction "MH1_MH1") (pintype "passive"))
      (node (ref "J12") (pin "MH2") (pinfunction "MH2_MH2") (pintype "passive"))
      (node (ref "J13") (pin "A1") (pinfunction "A1_A1") (pintype "passive"))
      (node (ref "J13") (pin "A10") (pinfunction "A10_A10") (pintype "passive"))
      (node (ref "J13") (pin "A13") (pinfunction "A13_A13") (pintype "passive"))
      (node (ref "J13") (pin "A15") (pinfunction "A15_A15") (pintype "passive"))
      (node (ref "J13") (pin "A32") (pinfunction "A32_A32") (pintype "passive"))
      (node (ref "J13") (pin "A4") (pinfunction "A4_A4") (pintype "passive"))
      (node (ref "J13") (pin "A7") (pinfunction "A7_A7") (pintype "passive"))
      (node (ref "J13") (pin "C1") (pinfunction "C1_C1") (pintype "passive"))
      (node (ref "J13") (pin "C10") (pinfunction "C10_C10") (pintype "passive"))
      (node (ref "J13") (pin "C13") (pinfunction "C13_C13") (pintype "passive"))
      (node (ref "J13") (pin "C15") (pinfunction "C15_C15") (pintype "passive"))
      (node (ref "J13") (pin "C32") (pinfunction "C32_C32") (pintype "passive"))
      (node (ref "J13") (pin "C4") (pinfunction "C4_C4") (pintype "passive"))
      (node (ref "J13") (pin "C7") (pinfunction "C7_C7") (pintype "passive"))
      (node (ref "J13") (pin "MH1") (pinfunction "MH1_MH1") (pintype "passive"))
      (node (ref "J13") (pin "MH2") (pinfunction "MH2_MH2") (pintype "passive"))
      (node (ref "J14") (pin "A1") (pinfunction "A1_A1") (pintype "passive"))
      (node (ref "J14") (pin "A10") (pinfunction "A10_A10") (pintype "passive"))
      (node (ref "J14") (pin "A13") (pinfunction "A13_A13") (pintype "passive"))
      (node (ref "J14") (pin "A15") (pinfunction "A15_A15") (pintype "passive"))
      (node (ref "J14") (pin "A32") (pinfunction "A32_A32") (pintype "passive"))
      (node (ref "J14") (pin "A4") (pinfunction "A4_A4") (pintype "passive"))
      (node (ref "J14") (pin "A7") (pinfunction "A7_A7") (pintype "passive"))
      (node (ref "J14") (pin "C1") (pinfunction "C1_C1") (pintype "passive"))
      (node (ref "J14") (pin "C10") (pinfunction "C10_C10") (pintype "passive"))
      (node (ref "J14") (pin "C13") (pinfunction "C13_C13") (pintype "passive"))
      (node (ref "J14") (pin "C15") (pinfunction "C15_C15") (pintype "passive"))
      (node (ref "J14") (pin "C32") (pinfunction "C32_C32") (pintype "passive"))
      (node (ref "J14") (pin "C4") (pinfunction "C4_C4") (pintype "passive"))
      (node (ref "J14") (pin "C7") (pinfunction "C7_C7") (pintype "passive"))
      (node (ref "J14") (pin "MH1") (pinfunction "MH1_MH1") (pintype "passive"))
      (node (ref "J14") (pin "MH2") (pinfunction "MH2_MH2") (pintype "passive"))
      (node (ref "J15") (pin "A1") (pinfunction "A1_A1") (pintype "passive"))
      (node (ref "J15") (pin "A10") (pinfunction "A10_A10") (pintype "passive"))
      (node (ref "J15") (pin "A13") (pinfunction "A13_A13") (pintype "passive"))
      (node (ref "J15") (pin "A15") (pinfunction "A15_A15") (pintype "passive"))
      (node (ref "J15") (pin "A32") (pinfunction "A32_A32") (pintype "passive"))
      (node (ref "J15") (pin "A4") (pinfunction "A4_A4") (pintype "passive"))
      (node (ref "J15") (pin "A7") (pinfunction "A7_A7") (pintype "passive"))
      (node (ref "J15") (pin "C1") (pinfunction "C1_C1") (pintype "passive"))
      (node (ref "J15") (pin "C10") (pinfunction "C10_C10") (pintype "passive"))
      (node (ref "J15") (pin "C13") (pinfunction "C13_C13") (pintype "passive"))
      (node (ref "J15") (pin "C15") (pinfunction "C15_C15") (pintype "passive"))
      (node (ref "J15") (pin "C32") (pinfunction "C32_C32") (pintype "passive"))
      (node (ref "J15") (pin "C4") (pinfunction "C4_C4") (pintype "passive"))
      (node (ref "J15") (pin "C7") (pinfunction "C7_C7") (pintype "passive"))
      (node (ref "J15") (pin "MH1") (pinfunction "MH1_MH1") (pintype "passive"))
      (node (ref "J15") (pin "MH2") (pinfunction "MH2_MH2") (pintype "passive"))
      (node (ref "J16") (pin "A1") (pinfunction "A1_A1") (pintype "passive"))
      (node (ref "J16") (pin "A10") (pinfunction "A10_A10") (pintype "passive"))
      (node (ref "J16") (pin "A13") (pinfunction "A13_A13") (pintype "passive"))
      (node (ref "J16") (pin "A15") (pinfunction "A15_A15") (pintype "passive"))
      (node (ref "J16") (pin "A32") (pinfunction "A32_A32") (pintype "passive"))
      (node (ref "J16") (pin "A4") (pinfunction "A4_A4") (pintype "passive"))
      (node (ref "J16") (pin "A7") (pinfunction "A7_A7") (pintype "passive"))
      (node (ref "J16") (pin "C1") (pinfunction "C1_C1") (pintype "passive"))
      (node (ref "J16") (pin "C10") (pinfunction "C10_C10") (pintype "passive"))
      (node (ref "J16") (pin "C13") (pinfunction "C13_C13") (pintype "passive"))
      (node (ref "J16") (pin "C15") (pinfunction "C15_C15") (pintype "passive"))
      (node (ref "J16") (pin "C32") (pinfunction "C32_C32") (pintype "passive"))
      (node (ref "J16") (pin "C4") (pinfunction "C4_C4") (pintype "passive"))
      (node (ref "J16") (pin "C7") (pinfunction "C7_C7") (pintype "passive"))
      (node (ref "J16") (pin "MH1") (pinfunction "MH1_MH1") (pintype "passive"))
      (node (ref "J16") (pin "MH2") (pinfunction "MH2_MH2") (pintype "passive"))
      (node (ref "J2") (pin "A1") (pinfunction "A1_A1") (pintype "passive"))
      (node (ref "J2") (pin "A10") (pinfunction "A10_A10") (pintype "passive"))
      (node (ref "J2") (pin "A13") (pinfunction "A13_A13") (pintype "passive"))
      (node (ref "J2") (pin "A15") (pinfunction "A15_A15") (pintype "passive"))
      (node (ref "J2") (pin "A32") (pinfunction "A32_A32") (pintype "passive"))
      (node (ref "J2") (pin "A4") (pinfunction "A4_A4") (pintype "passive"))
      (node (ref "J2") (pin "A7") (pinfunction "A7_A7") (pintype "passive"))
      (node (ref "J2") (pin "C1") (pinfunction "C1_C1") (pintype "passive"))
      (node (ref "J2") (pin "C10") (pinfunction "C10_C10") (pintype "passive"))
      (node (ref "J2") (pin "C13") (pinfunction "C13_C13") (pintype "passive"))
      (node (ref "J2") (pin "C15") (pinfunction "C15_C15") (pintype "passive"))
      (node (ref "J2") (pin "C32") (pinfunction "C32_C32") (pintype "passive"))
      (node (ref "J2") (pin "C4") (pinfunction "C4_C4") (pintype "passive"))
      (node (ref "J2") (pin "C7") (pinfunction "C7_C7") (pintype "passive"))
      (node (ref "J2") (pin "MH1") (pinfunction "MH1_MH1") (pintype "passive"))
      (node (ref "J2") (pin "MH2") (pinfunction "MH2_MH2") (pintype "passive"))
      (node (ref "J3") (pin "A1") (pinfunction "A1_A1") (pintype "passive"))
      (node (ref "J3") (pin "A10") (pinfunction "A10_A10") (pintype "passive"))
      (node (ref "J3") (pin "A13") (pinfunction "A13_A13") (pintype "passive"))
      (node (ref "J3") (pin "A15") (pinfunction "A15_A15") (pintype "passive"))
      (node (ref "J3") (pin "A32") (pinfunction "A32_A32") (pintype "passive"))
      (node (ref "J3") (pin "A4") (pinfunction "A4_A4") (pintype "passive"))
      (node (ref "J3") (pin "A7") (pinfunction "A7_A7") (pintype "passive"))
      (node (ref "J3") (pin "C1") (pinfunction "C1_C1") (pintype "passive"))
      (node (ref "J3") (pin "C10") (pinfunction "C10_C10") (pintype "passive"))
      (node (ref "J3") (pin "C13") (pinfunction "C13_C13") (pintype "passive"))
      (node (ref "J3") (pin "C15") (pinfunction "C15_C15") (pintype "passive"))
      (node (ref "J3") (pin "C32") (pinfunction "C32_C32") (pintype "passive"))
      (node (ref "J3") (pin "C4") (pinfunction "C4_C4") (pintype "passive"))
      (node (ref "J3") (pin "C7") (pinfunction "C7_C7") (pintype "passive"))
      (node (ref "J3") (pin "MH1") (pinfunction "MH1_MH1") (pintype "passive"))
      (node (ref "J3") (pin "MH2") (pinfunction "MH2_MH2") (pintype "passive"))
      (node (ref "J4") (pin "A1") (pinfunction "A1_A1") (pintype "passive"))
      (node (ref "J4") (pin "A10") (pinfunction "A10_A10") (pintype "passive"))
      (node (ref "J4") (pin "A13") (pinfunction "A13_A13") (pintype "passive"))
      (node (ref "J4") (pin "A15") (pinfunction "A15_A15") (pintype "passive"))
      (node (ref "J4") (pin "A32") (pinfunction "A32_A32") (pintype "passive"))
      (node (ref "J4") (pin "A4") (pinfunction "A4_A4") (pintype "passive"))
      (node (ref "J4") (pin "A7") (pinfunction "A7_A7") (pintype "passive"))
      (node (ref "J4") (pin "C1") (pinfunction "C1_C1") (pintype "passive"))
      (node (ref "J4") (pin "C10") (pinfunction "C10_C10") (pintype "passive"))
      (node (ref "J4") (pin "C13") (pinfunction "C13_C13") (pintype "passive"))
      (node (ref "J4") (pin "C15") (pinfunction "C15_C15") (pintype "passive"))
      (node (ref "J4") (pin "C32") (pinfunction "C32_C32") (pintype "passive"))
      (node (ref "J4") (pin "C4") (pinfunction "C4_C4") (pintype "passive"))
      (node (ref "J4") (pin "C7") (pinfunction "C7_C7") (pintype "passive"))
      (node (ref "J4") (pin "MH1") (pinfunction "MH1_MH1") (pintype "passive"))
      (node (ref "J4") (pin "MH2") (pinfunction "MH2_MH2") (pintype "passive"))
      (node (ref "J5") (pin "A1") (pinfunction "A1_A1") (pintype "passive"))
      (node (ref "J5") (pin "A10") (pinfunction "A10_A10") (pintype "passive"))
      (node (ref "J5") (pin "A13") (pinfunction "A13_A13") (pintype "passive"))
      (node (ref "J5") (pin "A15") (pinfunction "A15_A15") (pintype "passive"))
      (node (ref "J5") (pin "A32") (pinfunction "A32_A32") (pintype "passive"))
      (node (ref "J5") (pin "A4") (pinfunction "A4_A4") (pintype "passive"))
      (node (ref "J5") (pin "A7") (pinfunction "A7_A7") (pintype "passive"))
      (node (ref "J5") (pin "C1") (pinfunction "C1_C1") (pintype "passive"))
      (node (ref "J5") (pin "C10") (pinfunction "C10_C10") (pintype "passive"))
      (node (ref "J5") (pin "C13") (pinfunction "C13_C13") (pintype "passive"))
      (node (ref "J5") (pin "C15") (pinfunction "C15_C15") (pintype "passive"))
      (node (ref "J5") (pin "C32") (pinfunction "C32_C32") (pintype "passive"))
      (node (ref "J5") (pin "C4") (pinfunction "C4_C4") (pintype "passive"))
      (node (ref "J5") (pin "C7") (pinfunction "C7_C7") (pintype "passive"))
      (node (ref "J5") (pin "MH1") (pinfunction "MH1_MH1") (pintype "passive"))
      (node (ref "J5") (pin "MH2") (pinfunction "MH2_MH2") (pintype "passive"))
      (node (ref "J6") (pin "A1") (pinfunction "A1_A1") (pintype "passive"))
      (node (ref "J6") (pin "A10") (pinfunction "A10_A10") (pintype "passive"))
      (node (ref "J6") (pin "A13") (pinfunction "A13_A13") (pintype "passive"))
      (node (ref "J6") (pin "A15") (pinfunction "A15_A15") (pintype "passive"))
      (node (ref "J6") (pin "A32") (pinfunction "A32_A32") (pintype "passive"))
      (node (ref "J6") (pin "A4") (pinfunction "A4_A4") (pintype "passive"))
      (node (ref "J6") (pin "A7") (pinfunction "A7_A7") (pintype "passive"))
      (node (ref "J6") (pin "C1") (pinfunction "C1_C1") (pintype "passive"))
      (node (ref "J6") (pin "C10") (pinfunction "C10_C10") (pintype "passive"))
      (node (ref "J6") (pin "C13") (pinfunction "C13_C13") (pintype "passive"))
      (node (ref "J6") (pin "C15") (pinfunction "C15_C15") (pintype "passive"))
      (node (ref "J6") (pin "C32") (pinfunction "C32_C32") (pintype "passive"))
      (node (ref "J6") (pin "C4") (pinfunction "C4_C4") (pintype "passive"))
      (node (ref "J6") (pin "C7") (pinfunction "C7_C7") (pintype "passive"))
      (node (ref "J6") (pin "MH1") (pinfunction "MH1_MH1") (pintype "passive"))
      (node (ref "J6") (pin "MH2") (pinfunction "MH2_MH2") (pintype "passive"))
      (node (ref "J7") (pin "A1") (pinfunction "A1_A1") (pintype "passive"))
      (node (ref "J7") (pin "A10") (pinfunction "A10_A10") (pintype "passive"))
      (node (ref "J7") (pin "A13") (pinfunction "A13_A13") (pintype "passive"))
      (node (ref "J7") (pin "A15") (pinfunction "A15_A15") (pintype "passive"))
      (node (ref "J7") (pin "A32") (pinfunction "A32_A32") (pintype "passive"))
      (node (ref "J7") (pin "A4") (pinfunction "A4_A4") (pintype "passive"))
      (node (ref "J7") (pin "A7") (pinfunction "A7_A7") (pintype "passive"))
      (node (ref "J7") (pin "C1") (pinfunction "C1_C1") (pintype "passive"))
      (node (ref "J7") (pin "C10") (pinfunction "C10_C10") (pintype "passive"))
      (node (ref "J7") (pin "C13") (pinfunction "C13_C13") (pintype "passive"))
      (node (ref "J7") (pin "C15") (pinfunction "C15_C15") (pintype "passive"))
      (node (ref "J7") (pin "C32") (pinfunction "C32_C32") (pintype "passive"))
      (node (ref "J7") (pin "C4") (pinfunction "C4_C4") (pintype "passive"))
      (node (ref "J7") (pin "C7") (pinfunction "C7_C7") (pintype "passive"))
      (node (ref "J7") (pin "MH1") (pinfunction "MH1_MH1") (pintype "passive"))
      (node (ref "J7") (pin "MH2") (pinfunction "MH2_MH2") (pintype "passive"))
      (node (ref "J8") (pin "A1") (pinfunction "A1_A1") (pintype "passive"))
      (node (ref "J8") (pin "A10") (pinfunction "A10_A10") (pintype "passive"))
      (node (ref "J8") (pin "A13") (pinfunction "A13_A13") (pintype "passive"))
      (node (ref "J8") (pin "A15") (pinfunction "A15_A15") (pintype "passive"))
      (node (ref "J8") (pin "A32") (pinfunction "A32_A32") (pintype "passive"))
      (node (ref "J8") (pin "A4") (pinfunction "A4_A4") (pintype "passive"))
      (node (ref "J8") (pin "A7") (pinfunction "A7_A7") (pintype "passive"))
      (node (ref "J8") (pin "C1") (pinfunction "C1_C1") (pintype "passive"))
      (node (ref "J8") (pin "C10") (pinfunction "C10_C10") (pintype "passive"))
      (node (ref "J8") (pin "C13") (pinfunction "C13_C13") (pintype "passive"))
      (node (ref "J8") (pin "C15") (pinfunction "C15_C15") (pintype "passive"))
      (node (ref "J8") (pin "C32") (pinfunction "C32_C32") (pintype "passive"))
      (node (ref "J8") (pin "C4") (pinfunction "C4_C4") (pintype "passive"))
      (node (ref "J8") (pin "C7") (pinfunction "C7_C7") (pintype "passive"))
      (node (ref "J8") (pin "MH1") (pinfunction "MH1_MH1") (pintype "passive"))
      (node (ref "J8") (pin "MH2") (pinfunction "MH2_MH2") (pintype "passive"))
      (node (ref "J9") (pin "A1") (pinfunction "A1_A1") (pintype "passive"))
      (node (ref "J9") (pin "A10") (pinfunction "A10_A10") (pintype "passive"))
      (node (ref "J9") (pin "A13") (pinfunction "A13_A13") (pintype "passive"))
      (node (ref "J9") (pin "A15") (pinfunction "A15_A15") (pintype "passive"))
      (node (ref "J9") (pin "A32") (pinfunction "A32_A32") (pintype "passive"))
      (node (ref "J9") (pin "A4") (pinfunction "A4_A4") (pintype "passive"))
      (node (ref "J9") (pin "A7") (pinfunction "A7_A7") (pintype "passive"))
      (node (ref "J9") (pin "C1") (pinfunction "C1_C1") (pintype "passive"))
      (node (ref "J9") (pin "C10") (pinfunction "C10_C10") (pintype "passive"))
      (node (ref "J9") (pin "C13") (pinfunction "C13_C13") (pintype "passive"))
      (node (ref "J9") (pin "C15") (pinfunction "C15_C15") (pintype "passive"))
      (node (ref "J9") (pin "C32") (pinfunction "C32_C32") (pintype "passive"))
      (node (ref "J9") (pin "C4") (pinfunction "C4_C4") (pintype "passive"))
      (node (ref "J9") (pin "C7") (pinfunction "C7_C7") (pintype "passive"))
      (node (ref "J9") (pin "MH1") (pinfunction "MH1_MH1") (pintype "passive"))
      (node (ref "J9") (pin "MH2") (pinfunction "MH2_MH2") (pintype "passive"))
    )
    (net (code "26") (name "Net-(D1-A)") (class "Default")
      (node (ref "D1") (pin "1") (pinfunction "A_1") (pintype "passive"))
      (node (ref "R1") (pin "1") (pinfunction "1_1") (pintype "passive"))
    )
    (net (code "27") (name "Net-(D2-A)") (class "Default")
      (node (ref "D2") (pin "1") (pinfunction "A_1") (pintype "passive"))
      (node (ref "R2") (pin "1") (pinfunction "1_1") (pintype "passive"))
    )
    (net (code "28") (name "Net-(J1-PadC16)") (class "Default")
      (node (ref "J1") (pin "C16") (pinfunction "C16_C16") (pintype "passive"))
      (node (ref "J2") (pin "A16") (pinfunction "A16_A16") (pintype "passive"))
    )
    (net (code "29") (name "Net-(J1-PadC17)") (class "Default")
      (node (ref "J1") (pin "C17") (pinfunction "C17_C17") (pintype "passive"))
      (node (ref "J2") (pin "A17") (pinfunction "A17_A17") (pintype "passive"))
    )
    (net (code "30") (name "Net-(J1-PadC18)") (class "Default")
      (node (ref "J1") (pin "C18") (pinfunction "C18_C18") (pintype "passive"))
      (node (ref "J2") (pin "A18") (pinfunction "A18_A18") (pintype "passive"))
    )
    (net (code "31") (name "Net-(J1-PadC19)") (class "Default")
      (node (ref "J1") (pin "C19") (pinfunction "C19_C19") (pintype "passive"))
      (node (ref "J2") (pin "A19") (pinfunction "A19_A19") (pintype "passive"))
    )
    (net (code "32") (name "Net-(J1-PadC20)") (class "Default")
      (node (ref "J1") (pin "C20") (pinfunction "C20_C20") (pintype "passive"))
      (node (ref "J2") (pin "A20") (pinfunction "A20_A20") (pintype "passive"))
    )
    (net (code "33") (name "Net-(J1-PadC21)") (class "Default")
      (node (ref "J1") (pin "C21") (pinfunction "C21_C21") (pintype "passive"))
      (node (ref "J2") (pin "A21") (pinfunction "A21_A21") (pintype "passive"))
    )
    (net (code "34") (name "Net-(J1-PadC22)") (class "Default")
      (node (ref "J1") (pin "C22") (pinfunction "C22_C22") (pintype "passive"))
      (node (ref "J2") (pin "A22") (pinfunction "A22_A22") (pintype "passive"))
    )
    (net (code "35") (name "Net-(J1-PadC23)") (class "Default")
      (node (ref "J1") (pin "C23") (pinfunction "C23_C23") (pintype "passive"))
      (node (ref "J2") (pin "A23") (pinfunction "A23_A23") (pintype "passive"))
    )
    (net (code "36") (name "Net-(J1-PadC24)") (class "Default")
      (node (ref "J1") (pin "C24") (pinfunction "C24_C24") (pintype "passive"))
      (node (ref "J2") (pin "A24") (pinfunction "A24_A24") (pintype "passive"))
    )
    (net (code "37") (name "Net-(J1-PadC25)") (class "Default")
      (node (ref "J1") (pin "C25") (pinfunction "C25_C25") (pintype "passive"))
      (node (ref "J2") (pin "A25") (pinfunction "A25_A25") (pintype "passive"))
    )
    (net (code "38") (name "Net-(J1-PadC26)") (class "Default")
      (node (ref "J1") (pin "C26") (pinfunction "C26_C26") (pintype "passive"))
      (node (ref "J2") (pin "A26") (pinfunction "A26_A26") (pintype "passive"))
    )
    (net (code "39") (name "Net-(J1-PadC27)") (class "Default")
      (node (ref "J1") (pin "C27") (pinfunction "C27_C27") (pintype "passive"))
      (node (ref "J2") (pin "A27") (pinfunction "A27_A27") (pintype "passive"))
    )
    (net (code "40") (name "Net-(J1-PadC28)") (class "Default")
      (node (ref "J1") (pin "C28") (pinfunction "C28_C28") (pintype "passive"))
      (node (ref "J2") (pin "A28") (pinfunction "A28_A28") (pintype "passive"))
    )
    (net (code "41") (name "Net-(J1-PadC29)") (class "Default")
      (node (ref "J1") (pin "C29") (pinfunction "C29_C29") (pintype "passive"))
      (node (ref "J2") (pin "A29") (pinfunction "A29_A29") (pintype "passive"))
    )
    (net (code "42") (name "Net-(J1-PadC30)") (class "Default")
      (node (ref "J1") (pin "C30") (pinfunction "C30_C30") (pintype "passive"))
      (node (ref "J2") (pin "A30") (pinfunction "A30_A30") (pintype "passive"))
    )
    (net (code "43") (name "Net-(J1-PadC31)") (class "Default")
      (node (ref "J1") (pin "C31") (pinfunction "C31_C31") (pintype "passive"))
      (node (ref "J2") (pin "A31") (pinfunction "A31_A31") (pintype "passive"))
    )
    (net (code "44") (name "Net-(J2-PadC16)") (class "Default")
      (node (ref "J2") (pin "C16") (pinfunction "C16_C16") (pintype "passive"))
      (node (ref "J3") (pin "A16") (pinfunction "A16_A16") (pintype "passive"))
    )
    (net (code "45") (name "Net-(J2-PadC17)") (class "Default")
      (node (ref "J2") (pin "C17") (pinfunction "C17_C17") (pintype "passive"))
      (node (ref "J3") (pin "A17") (pinfunction "A17_A17") (pintype "passive"))
    )
    (net (code "46") (name "Net-(J2-PadC18)") (class "Default")
      (node (ref "J2") (pin "C18") (pinfunction "C18_C18") (pintype "passive"))
      (node (ref "J3") (pin "A18") (pinfunction "A18_A18") (pintype "passive"))
    )
    (net (code "47") (name "Net-(J2-PadC19)") (class "Default")
      (node (ref "J2") (pin "C19") (pinfunction "C19_C19") (pintype "passive"))
      (node (ref "J3") (pin "A19") (pinfunction "A19_A19") (pintype "passive"))
    )
    (net (code "48") (name "Net-(J2-PadC20)") (class "Default")
      (node (ref "J2") (pin "C20") (pinfunction "C20_C20") (pintype "passive"))
      (node (ref "J3") (pin "A20") (pinfunction "A20_A20") (pintype "passive"))
    )
    (net (code "49") (name "Net-(J2-PadC21)") (class "Default")
      (node (ref "J2") (pin "C21") (pinfunction "C21_C21") (pintype "passive"))
      (node (ref "J3") (pin "A21") (pinfunction "A21_A21") (pintype "passive"))
    )
    (net (code "50") (name "Net-(J2-PadC22)") (class "Default")
      (node (ref "J2") (pin "C22") (pinfunction "C22_C22") (pintype "passive"))
      (node (ref "J3") (pin "A22") (pinfunction "A22_A22") (pintype "passive"))
    )
    (net (code "51") (name "Net-(J2-PadC23)") (class "Default")
      (node (ref "J2") (pin "C23") (pinfunction "C23_C23") (pintype "passive"))
      (node (ref "J3") (pin "A23") (pinfunction "A23_A23") (pintype "passive"))
    )
    (net (code "52") (name "Net-(J2-PadC24)") (class "Default")
      (node (ref "J2") (pin "C24") (pinfunction "C24_C24") (pintype "passive"))
      (node (ref "J3") (pin "A24") (pinfunction "A24_A24") (pintype "passive"))
    )
    (net (code "53") (name "Net-(J2-PadC25)") (class "Default")
      (node (ref "J2") (pin "C25") (pinfunction "C25_C25") (pintype "passive"))
      (node (ref "J3") (pin "A25") (pinfunction "A25_A25") (pintype "passive"))
    )
    (net (code "54") (name "Net-(J2-PadC26)") (class "Default")
      (node (ref "J2") (pin "C26") (pinfunction "C26_C26") (pintype "passive"))
      (node (ref "J3") (pin "A26") (pinfunction "A26_A26") (pintype "passive"))
    )
    (net (code "55") (name "Net-(J2-PadC27)") (class "Default")
      (node (ref "J2") (pin "C27") (pinfunction "C27_C27") (pintype "passive"))
      (node (ref "J3") (pin "A27") (pinfunction "A27_A27") (pintype "passive"))
    )
    (net (code "56") (name "Net-(J2-PadC28)") (class "Default")
      (node (ref "J2") (pin "C28") (pinfunction "C28_C28") (pintype "passive"))
      (node (ref "J3") (pin "A28") (pinfunction "A28_A28") (pintype "passive"))
    )
    (net (code "57") (name "Net-(J2-PadC29)") (class "Default")
      (node (ref "J2") (pin "C29") (pinfunction "C29_C29") (pintype "passive"))
      (node (ref "J3") (pin "A29") (pinfunction "A29_A29") (pintype "passive"))
    )
    (net (code "58") (name "Net-(J2-PadC30)") (class "Default")
      (node (ref "J2") (pin "C30") (pinfunction "C30_C30") (pintype "passive"))
      (node (ref "J3") (pin "A30") (pinfunction "A30_A30") (pintype "passive"))
    )
    (net (code "59") (name "Net-(J2-PadC31)") (class "Default")
      (node (ref "J2") (pin "C31") (pinfunction "C31_C31") (pintype "passive"))
      (node (ref "J3") (pin "A31") (pinfunction "A31_A31") (pintype "passive"))
    )
    (net (code "60") (name "Net-(J3-PadC16)") (class "Default")
      (node (ref "J3") (pin "C16") (pinfunction "C16_C16") (pintype "passive"))
      (node (ref "J4") (pin "A16") (pinfunction "A16_A16") (pintype "passive"))
    )
    (net (code "61") (name "Net-(J3-PadC17)") (class "Default")
      (node (ref "J3") (pin "C17") (pinfunction "C17_C17") (pintype "passive"))
      (node (ref "J4") (pin "A17") (pinfunction "A17_A17") (pintype "passive"))
    )
    (net (code "62") (name "Net-(J3-PadC18)") (class "Default")
      (node (ref "J3") (pin "C18") (pinfunction "C18_C18") (pintype "passive"))
      (node (ref "J4") (pin "A18") (pinfunction "A18_A18") (pintype "passive"))
    )
    (net (code "63") (name "Net-(J3-PadC19)") (class "Default")
      (node (ref "J3") (pin "C19") (pinfunction "C19_C19") (pintype "passive"))
      (node (ref "J4") (pin "A19") (pinfunction "A19_A19") (pintype "passive"))
    )
    (net (code "64") (name "Net-(J3-PadC20)") (class "Default")
      (node (ref "J3") (pin "C20") (pinfunction "C20_C20") (pintype "passive"))
      (node (ref "J4") (pin "A20") (pinfunction "A20_A20") (pintype "passive"))
    )
    (net (code "65") (name "Net-(J3-PadC21)") (class "Default")
      (node (ref "J3") (pin "C21") (pinfunction "C21_C21") (pintype "passive"))
      (node (ref "J4") (pin "A21") (pinfunction "A21_A21") (pintype "passive"))
    )
    (net (code "66") (name "Net-(J3-PadC22)") (class "Default")
      (node (ref "J3") (pin "C22") (pinfunction "C22_C22") (pintype "passive"))
      (node (ref "J4") (pin "A22") (pinfunction "A22_A22") (pintype "passive"))
    )
    (net (code "67") (name "Net-(J3-PadC23)") (class "Default")
      (node (ref "J3") (pin "C23") (pinfunction "C23_C23") (pintype "passive"))
      (node (ref "J4") (pin "A23") (pinfunction "A23_A23") (pintype "passive"))
    )
    (net (code "68") (name "Net-(J3-PadC24)") (class "Default")
      (node (ref "J3") (pin "C24") (pinfunction "C24_C24") (pintype "passive"))
      (node (ref "J4") (pin "A24") (pinfunction "A24_A24") (pintype "passive"))
    )
    (net (code "69") (name "Net-(J3-PadC25)") (class "Default")
      (node (ref "J3") (pin "C25") (pinfunction "C25_C25") (pintype "passive"))
      (node (ref "J4") (pin "A25") (pinfunction "A25_A25") (pintype "passive"))
    )
    (net (code "70") (name "Net-(J3-PadC26)") (class "Default")
      (node (ref "J3") (pin "C26") (pinfunction "C26_C26") (pintype "passive"))
      (node (ref "J4") (pin "A26") (pinfunction "A26_A26") (pintype "passive"))
    )
    (net (code "71") (name "Net-(J3-PadC27)") (class "Default")
      (node (ref "J3") (pin "C27") (pinfunction "C27_C27") (pintype "passive"))
      (node (ref "J4") (pin "A27") (pinfunction "A27_A27") (pintype "passive"))
    )
    (net (code "72") (name "Net-(J3-PadC28)") (class "Default")
      (node (ref "J3") (pin "C28") (pinfunction "C28_C28") (pintype "passive"))
      (node (ref "J4") (pin "A28") (pinfunction "A28_A28") (pintype "passive"))
    )
    (net (code "73") (name "Net-(J3-PadC29)") (class "Default")
      (node (ref "J3") (pin "C29") (pinfunction "C29_C29") (pintype "passive"))
      (node (ref "J4") (pin "A29") (pinfunction "A29_A29") (pintype "passive"))
    )
    (net (code "74") (name "Net-(J3-PadC30)") (class "Default")
      (node (ref "J3") (pin "C30") (pinfunction "C30_C30") (pintype "passive"))
      (node (ref "J4") (pin "A30") (pinfunction "A30_A30") (pintype "passive"))
    )
    (net (code "75") (name "Net-(J3-PadC31)") (class "Default")
      (node (ref "J3") (pin "C31") (pinfunction "C31_C31") (pintype "passive"))
      (node (ref "J4") (pin "A31") (pinfunction "A31_A31") (pintype "passive"))
    )
    (net (code "76") (name "Net-(J4-PadC16)") (class "Default")
      (node (ref "J4") (pin "C16") (pinfunction "C16_C16") (pintype "passive"))
      (node (ref "J5") (pin "A16") (pinfunction "A16_A16") (pintype "passive"))
    )
    (net (code "77") (name "Net-(J4-PadC17)") (class "Default")
      (node (ref "J4") (pin "C17") (pinfunction "C17_C17") (pintype "passive"))
      (node (ref "J5") (pin "A17") (pinfunction "A17_A17") (pintype "passive"))
    )
    (net (code "78") (name "Net-(J4-PadC18)") (class "Default")
      (node (ref "J4") (pin "C18") (pinfunction "C18_C18") (pintype "passive"))
      (node (ref "J5") (pin "A18") (pinfunction "A18_A18") (pintype "passive"))
    )
    (net (code "79") (name "Net-(J4-PadC19)") (class "Default")
      (node (ref "J4") (pin "C19") (pinfunction "C19_C19") (pintype "passive"))
      (node (ref "J5") (pin "A19") (pinfunction "A19_A19") (pintype "passive"))
    )
    (net (code "80") (name "Net-(J4-PadC20)") (class "Default")
      (node (ref "J4") (pin "C20") (pinfunction "C20_C20") (pintype "passive"))
      (node (ref "J5") (pin "A20") (pinfunction "A20_A20") (pintype "passive"))
    )
    (net (code "81") (name "Net-(J4-PadC21)") (class "Default")
      (node (ref "J4") (pin "C21") (pinfunction "C21_C21") (pintype "passive"))
      (node (ref "J5") (pin "A21") (pinfunction "A21_A21") (pintype "passive"))
    )
    (net (code "82") (name "Net-(J4-PadC22)") (class "Default")
      (node (ref "J4") (pin "C22") (pinfunction "C22_C22") (pintype "passive"))
      (node (ref "J5") (pin "A22") (pinfunction "A22_A22") (pintype "passive"))
    )
    (net (code "83") (name "Net-(J4-PadC23)") (class "Default")
      (node (ref "J4") (pin "C23") (pinfunction "C23_C23") (pintype "passive"))
      (node (ref "J5") (pin "A23") (pinfunction "A23_A23") (pintype "passive"))
    )
    (net (code "84") (name "Net-(J4-PadC24)") (class "Default")
      (node (ref "J4") (pin "C24") (pinfunction "C24_C24") (pintype "passive"))
      (node (ref "J5") (pin "A24") (pinfunction "A24_A24") (pintype "passive"))
    )
    (net (code "85") (name "Net-(J4-PadC25)") (class "Default")
      (node (ref "J4") (pin "C25") (pinfunction "C25_C25") (pintype "passive"))
      (node (ref "J5") (pin "A25") (pinfunction "A25_A25") (pintype "passive"))
    )
    (net (code "86") (name "Net-(J4-PadC26)") (class "Default")
      (node (ref "J4") (pin "C26") (pinfunction "C26_C26") (pintype "passive"))
      (node (ref "J5") (pin "A26") (pinfunction "A26_A26") (pintype "passive"))
    )
    (net (code "87") (name "Net-(J4-PadC27)") (class "Default")
      (node (ref "J4") (pin "C27") (pinfunction "C27_C27") (pintype "passive"))
      (node (ref "J5") (pin "A27") (pinfunction "A27_A27") (pintype "passive"))
    )
    (net (code "88") (name "Net-(J4-PadC28)") (class "Default")
      (node (ref "J4") (pin "C28") (pinfunction "C28_C28") (pintype "passive"))
      (node (ref "J5") (pin "A28") (pinfunction "A28_A28") (pintype "passive"))
    )
    (net (code "89") (name "Net-(J4-PadC29)") (class "Default")
      (node (ref "J4") (pin "C29") (pinfunction "C29_C29") (pintype "passive"))
      (node (ref "J5") (pin "A29") (pinfunction "A29_A29") (pintype "passive"))
    )
    (net (code "90") (name "Net-(J4-PadC30)") (class "Default")
      (node (ref "J4") (pin "C30") (pinfunction "C30_C30") (pintype "passive"))
      (node (ref "J5") (pin "A30") (pinfunction "A30_A30") (pintype "passive"))
    )
    (net (code "91") (name "Net-(J4-PadC31)") (class "Default")
      (node (ref "J4") (pin "C31") (pinfunction "C31_C31") (pintype "passive"))
      (node (ref "J5") (pin "A31") (pinfunction "A31_A31") (pintype "passive"))
    )
    (net (code "92") (name "Net-(J5-PadC16)") (class "Default")
      (node (ref "J5") (pin "C16") (pinfunction "C16_C16") (pintype "passive"))
      (node (ref "J6") (pin "A16") (pinfunction "A16_A16") (pintype "passive"))
    )
    (net (code "93") (name "Net-(J5-PadC17)") (class "Default")
      (node (ref "J5") (pin "C17") (pinfunction "C17_C17") (pintype "passive"))
      (node (ref "J6") (pin "A17") (pinfunction "A17_A17") (pintype "passive"))
    )
    (net (code "94") (name "Net-(J5-PadC18)") (class "Default")
      (node (ref "J5") (pin "C18") (pinfunction "C18_C18") (pintype "passive"))
      (node (ref "J6") (pin "A18") (pinfunction "A18_A18") (pintype "passive"))
    )
    (net (code "95") (name "Net-(J5-PadC19)") (class "Default")
      (node (ref "J5") (pin "C19") (pinfunction "C19_C19") (pintype "passive"))
      (node (ref "J6") (pin "A19") (pinfunction "A19_A19") (pintype "passive"))
    )
    (net (code "96") (name "Net-(J5-PadC20)") (class "Default")
      (node (ref "J5") (pin "C20") (pinfunction "C20_C20") (pintype "passive"))
      (node (ref "J6") (pin "A20") (pinfunction "A20_A20") (pintype "passive"))
    )
    (net (code "97") (name "Net-(J5-PadC21)") (class "Default")
      (node (ref "J5") (pin "C21") (pinfunction "C21_C21") (pintype "passive"))
      (node (ref "J6") (pin "A21") (pinfunction "A21_A21") (pintype "passive"))
    )
    (net (code "98") (name "Net-(J5-PadC22)") (class "Default")
      (node (ref "J5") (pin "C22") (pinfunction "C22_C22") (pintype "passive"))
      (node (ref "J6") (pin "A22") (pinfunction "A22_A22") (pintype "passive"))
    )
    (net (code "99") (name "Net-(J5-PadC23)") (class "Default")
      (node (ref "J5") (pin "C23") (pinfunction "C23_C23") (pintype "passive"))
      (node (ref "J6") (pin "A23") (pinfunction "A23_A23") (pintype "passive"))
    )
    (net (code "100") (name "Net-(J5-PadC24)") (class "Default")
      (node (ref "J5") (pin "C24") (pinfunction "C24_C24") (pintype "passive"))
      (node (ref "J6") (pin "A24") (pinfunction "A24_A24") (pintype "passive"))
    )
    (net (code "101") (name "Net-(J5-PadC25)") (class "Default")
      (node (ref "J5") (pin "C25") (pinfunction "C25_C25") (pintype "passive"))
      (node (ref "J6") (pin "A25") (pinfunction "A25_A25") (pintype "passive"))
    )
    (net (code "102") (name "Net-(J5-PadC26)") (class "Default")
      (node (ref "J5") (pin "C26") (pinfunction "C26_C26") (pintype "passive"))
      (node (ref "J6") (pin "A26") (pinfunction "A26_A26") (pintype "passive"))
    )
    (net (code "103") (name "Net-(J5-PadC27)") (class "Default")
      (node (ref "J5") (pin "C27") (pinfunction "C27_C27") (pintype "passive"))
      (node (ref "J6") (pin "A27") (pinfunction "A27_A27") (pintype "passive"))
    )
    (net (code "104") (name "Net-(J5-PadC28)") (class "Default")
      (node (ref "J5") (pin "C28") (pinfunction "C28_C28") (pintype "passive"))
      (node (ref "J6") (pin "A28") (pinfunction "A28_A28") (pintype "passive"))
    )
    (net (code "105") (name "Net-(J5-PadC29)") (class "Default")
      (node (ref "J5") (pin "C29") (pinfunction "C29_C29") (pintype "passive"))
      (node (ref "J6") (pin "A29") (pinfunction "A29_A29") (pintype "passive"))
    )
    (net (code "106") (name "Net-(J5-PadC30)") (class "Default")
      (node (ref "J5") (pin "C30") (pinfunction "C30_C30") (pintype "passive"))
      (node (ref "J6") (pin "A30") (pinfunction "A30_A30") (pintype "passive"))
    )
    (net (code "107") (name "Net-(J5-PadC31)") (class "Default")
      (node (ref "J5") (pin "C31") (pinfunction "C31_C31") (pintype "passive"))
      (node (ref "J6") (pin "A31") (pinfunction "A31_A31") (pintype "passive"))
    )
    (net (code "108") (name "Net-(J6-PadC16)") (class "Default")
      (node (ref "J6") (pin "C16") (pinfunction "C16_C16") (pintype "passive"))
      (node (ref "J7") (pin "A16") (pinfunction "A16_A16") (pintype "passive"))
    )
    (net (code "109") (name "Net-(J6-PadC17)") (class "Default")
      (node (ref "J6") (pin "C17") (pinfunction "C17_C17") (pintype "passive"))
      (node (ref "J7") (pin "A17") (pinfunction "A17_A17") (pintype "passive"))
    )
    (net (code "110") (name "Net-(J6-PadC18)") (class "Default")
      (node (ref "J6") (pin "C18") (pinfunction "C18_C18") (pintype "passive"))
      (node (ref "J7") (pin "A18") (pinfunction "A18_A18") (pintype "passive"))
    )
    (net (code "111") (name "Net-(J6-PadC19)") (class "Default")
      (node (ref "J6") (pin "C19") (pinfunction "C19_C19") (pintype "passive"))
      (node (ref "J7") (pin "A19") (pinfunction "A19_A19") (pintype "passive"))
    )
    (net (code "112") (name "Net-(J6-PadC20)") (class "Default")
      (node (ref "J6") (pin "C20") (pinfunction "C20_C20") (pintype "passive"))
      (node (ref "J7") (pin "A20") (pinfunction "A20_A20") (pintype "passive"))
    )
    (net (code "113") (name "Net-(J6-PadC21)") (class "Default")
      (node (ref "J6") (pin "C21") (pinfunction "C21_C21") (pintype "passive"))
      (node (ref "J7") (pin "A21") (pinfunction "A21_A21") (pintype "passive"))
    )
    (net (code "114") (name "Net-(J6-PadC22)") (class "Default")
      (node (ref "J6") (pin "C22") (pinfunction "C22_C22") (pintype "passive"))
      (node (ref "J7") (pin "A22") (pinfunction "A22_A22") (pintype "passive"))
    )
    (net (code "115") (name "Net-(J6-PadC23)") (class "Default")
      (node (ref "J6") (pin "C23") (pinfunction "C23_C23") (pintype "passive"))
      (node (ref "J7") (pin "A23") (pinfunction "A23_A23") (pintype "passive"))
    )
    (net (code "116") (name "Net-(J6-PadC24)") (class "Default")
      (node (ref "J6") (pin "C24") (pinfunction "C24_C24") (pintype "passive"))
      (node (ref "J7") (pin "A24") (pinfunction "A24_A24") (pintype "passive"))
    )
    (net (code "117") (name "Net-(J6-PadC25)") (class "Default")
      (node (ref "J6") (pin "C25") (pinfunction "C25_C25") (pintype "passive"))
      (node (ref "J7") (pin "A25") (pinfunction "A25_A25") (pintype "passive"))
    )
    (net (code "118") (name "Net-(J6-PadC26)") (class "Default")
      (node (ref "J6") (pin "C26") (pinfunction "C26_C26") (pintype "passive"))
      (node (ref "J7") (pin "A26") (pinfunction "A26_A26") (pintype "passive"))
    )
    (net (code "119") (name "Net-(J6-PadC27)") (class "Default")
      (node (ref "J6") (pin "C27") (pinfunction "C27_C27") (pintype "passive"))
      (node (ref "J7") (pin "A27") (pinfunction "A27_A27") (pintype "passive"))
    )
    (net (code "120") (name "Net-(J6-PadC28)") (class "Default")
      (node (ref "J6") (pin "C28") (pinfunction "C28_C28") (pintype "passive"))
      (node (ref "J7") (pin "A28") (pinfunction "A28_A28") (pintype "passive"))
    )
    (net (code "121") (name "Net-(J6-PadC29)") (class "Default")
      (node (ref "J6") (pin "C29") (pinfunction "C29_C29") (pintype "passive"))
      (node (ref "J7") (pin "A29") (pinfunction "A29_A29") (pintype "passive"))
    )
    (net (code "122") (name "Net-(J6-PadC30)") (class "Default")
      (node (ref "J6") (pin "C30") (pinfunction "C30_C30") (pintype "passive"))
      (node (ref "J7") (pin "A30") (pinfunction "A30_A30") (pintype "passive"))
    )
    (net (code "123") (name "Net-(J6-PadC31)") (class "Default")
      (node (ref "J6") (pin "C31") (pinfunction "C31_C31") (pintype "passive"))
      (node (ref "J7") (pin "A31") (pinfunction "A31_A31") (pintype "passive"))
    )
    (net (code "124") (name "Net-(J7-PadC16)") (class "Default")
      (node (ref "J7") (pin "C16") (pinfunction "C16_C16") (pintype "passive"))
      (node (ref "J8") (pin "A16") (pinfunction "A16_A16") (pintype "passive"))
    )
    (net (code "125") (name "Net-(J7-PadC17)") (class "Default")
      (node (ref "J7") (pin "C17") (pinfunction "C17_C17") (pintype "passive"))
      (node (ref "J8") (pin "A17") (pinfunction "A17_A17") (pintype "passive"))
    )
    (net (code "126") (name "Net-(J7-PadC18)") (class "Default")
      (node (ref "J7") (pin "C18") (pinfunction "C18_C18") (pintype "passive"))
      (node (ref "J8") (pin "A18") (pinfunction "A18_A18") (pintype "passive"))
    )
    (net (code "127") (name "Net-(J7-PadC19)") (class "Default")
      (node (ref "J7") (pin "C19") (pinfunction "C19_C19") (pintype "passive"))
      (node (ref "J8") (pin "A19") (pinfunction "A19_A19") (pintype "passive"))
    )
    (net (code "128") (name "Net-(J7-PadC20)") (class "Default")
      (node (ref "J7") (pin "C20") (pinfunction "C20_C20") (pintype "passive"))
      (node (ref "J8") (pin "A20") (pinfunction "A20_A20") (pintype "passive"))
    )
    (net (code "129") (name "Net-(J7-PadC21)") (class "Default")
      (node (ref "J7") (pin "C21") (pinfunction "C21_C21") (pintype "passive"))
      (node (ref "J8") (pin "A21") (pinfunction "A21_A21") (pintype "passive"))
    )
    (net (code "130") (name "Net-(J7-PadC22)") (class "Default")
      (node (ref "J7") (pin "C22") (pinfunction "C22_C22") (pintype "passive"))
      (node (ref "J8") (pin "A22") (pinfunction "A22_A22") (pintype "passive"))
    )
    (net (code "131") (name "Net-(J7-PadC23)") (class "Default")
      (node (ref "J7") (pin "C23") (pinfunction "C23_C23") (pintype "passive"))
      (node (ref "J8") (pin "A23") (pinfunction "A23_A23") (pintype "passive"))
    )
    (net (code "132") (name "Net-(J7-PadC24)") (class "Default")
      (node (ref "J7") (pin "C24") (pinfunction "C24_C24") (pintype "passive"))
      (node (ref "J8") (pin "A24") (pinfunction "A24_A24") (pintype "passive"))
    )
    (net (code "133") (name "Net-(J7-PadC25)") (class "Default")
      (node (ref "J7") (pin "C25") (pinfunction "C25_C25") (pintype "passive"))
      (node (ref "J8") (pin "A25") (pinfunction "A25_A25") (pintype "passive"))
    )
    (net (code "134") (name "Net-(J7-PadC26)") (class "Default")
      (node (ref "J7") (pin "C26") (pinfunction "C26_C26") (pintype "passive"))
      (node (ref "J8") (pin "A26") (pinfunction "A26_A26") (pintype "passive"))
    )
    (net (code "135") (name "Net-(J7-PadC27)") (class "Default")
      (node (ref "J7") (pin "C27") (pinfunction "C27_C27") (pintype "passive"))
      (node (ref "J8") (pin "A27") (pinfunction "A27_A27") (pintype "passive"))
    )
    (net (code "136") (name "Net-(J7-PadC28)") (class "Default")
      (node (ref "J7") (pin "C28") (pinfunction "C28_C28") (pintype "passive"))
      (node (ref "J8") (pin "A28") (pinfunction "A28_A28") (pintype "passive"))
    )
    (net (code "137") (name "Net-(J7-PadC29)") (class "Default")
      (node (ref "J7") (pin "C29") (pinfunction "C29_C29") (pintype "passive"))
      (node (ref "J8") (pin "A29") (pinfunction "A29_A29") (pintype "passive"))
    )
    (net (code "138") (name "Net-(J7-PadC30)") (class "Default")
      (node (ref "J7") (pin "C30") (pinfunction "C30_C30") (pintype "passive"))
      (node (ref "J8") (pin "A30") (pinfunction "A30_A30") (pintype "passive"))
    )
    (net (code "139") (name "Net-(J7-PadC31)") (class "Default")
      (node (ref "J7") (pin "C31") (pinfunction "C31_C31") (pintype "passive"))
      (node (ref "J8") (pin "A31") (pinfunction "A31_A31") (pintype "passive"))
    )
    (net (code "140") (name "Net-(J10-PadA16)") (class "Default")
      (node (ref "J10") (pin "A16") (pinfunction "A16_A16") (pintype "passive"))
      (node (ref "J9") (pin "C16") (pinfunction "C16_C16") (pintype "passive"))
    )
    (net (code "141") (name "Net-(J10-PadA17)") (class "Default")
      (node (ref "J10") (pin "A17") (pinfunction "A17_A17") (pintype "passive"))
      (node (ref "J9") (pin "C17") (pinfunction "C17_C17") (pintype "passive"))
    )
    (net (code "142") (name "Net-(J10-PadA18)") (class "Default")
      (node (ref "J10") (pin "A18") (pinfunction "A18_A18") (pintype "passive"))
      (node (ref "J9") (pin "C18") (pinfunction "C18_C18") (pintype "passive"))
    )
    (net (code "143") (name "Net-(J10-PadA19)") (class "Default")
      (node (ref "J10") (pin "A19") (pinfunction "A19_A19") (pintype "passive"))
      (node (ref "J9") (pin "C19") (pinfunction "C19_C19") (pintype "passive"))
    )
    (net (code "144") (name "Net-(J10-PadA20)") (class "Default")
      (node (ref "J10") (pin "A20") (pinfunction "A20_A20") (pintype "passive"))
      (node (ref "J9") (pin "C20") (pinfunction "C20_C20") (pintype "passive"))
    )
    (net (code "145") (name "Net-(J10-PadA21)") (class "Default")
      (node (ref "J10") (pin "A21") (pinfunction "A21_A21") (pintype "passive"))
      (node (ref "J9") (pin "C21") (pinfunction "C21_C21") (pintype "passive"))
    )
    (net (code "146") (name "Net-(J10-PadA22)") (class "Default")
      (node (ref "J10") (pin "A22") (pinfunction "A22_A22") (pintype "passive"))
      (node (ref "J9") (pin "C22") (pinfunction "C22_C22") (pintype "passive"))
    )
    (net (code "147") (name "Net-(J10-PadA23)") (class "Default")
      (node (ref "J10") (pin "A23") (pinfunction "A23_A23") (pintype "passive"))
      (node (ref "J9") (pin "C23") (pinfunction "C23_C23") (pintype "passive"))
    )
    (net (code "148") (name "Net-(J10-PadA24)") (class "Default")
      (node (ref "J10") (pin "A24") (pinfunction "A24_A24") (pintype "passive"))
      (node (ref "J9") (pin "C24") (pinfunction "C24_C24") (pintype "passive"))
    )
    (net (code "149") (name "Net-(J10-PadA25)") (class "Default")
      (node (ref "J10") (pin "A25") (pinfunction "A25_A25") (pintype "passive"))
      (node (ref "J9") (pin "C25") (pinfunction "C25_C25") (pintype "passive"))
    )
    (net (code "150") (name "Net-(J10-PadA26)") (class "Default")
      (node (ref "J10") (pin "A26") (pinfunction "A26_A26") (pintype "passive"))
      (node (ref "J9") (pin "C26") (pinfunction "C26_C26") (pintype "passive"))
    )
    (net (code "151") (name "Net-(J10-PadA27)") (class "Default")
      (node (ref "J10") (pin "A27") (pinfunction "A27_A27") (pintype "passive"))
      (node (ref "J9") (pin "C27") (pinfunction "C27_C27") (pintype "passive"))
    )
    (net (code "152") (name "Net-(J10-PadA28)") (class "Default")
      (node (ref "J10") (pin "A28") (pinfunction "A28_A28") (pintype "passive"))
      (node (ref "J9") (pin "C28") (pinfunction "C28_C28") (pintype "passive"))
    )
    (net (code "153") (name "Net-(J10-PadA29)") (class "Default")
      (node (ref "J10") (pin "A29") (pinfunction "A29_A29") (pintype "passive"))
      (node (ref "J9") (pin "C29") (pinfunction "C29_C29") (pintype "passive"))
    )
    (net (code "154") (name "Net-(J10-PadA30)") (class "Default")
      (node (ref "J10") (pin "A30") (pinfunction "A30_A30") (pintype "passive"))
      (node (ref "J9") (pin "C30") (pinfunction "C30_C30") (pintype "passive"))
    )
    (net (code "155") (name "Net-(J10-PadA31)") (class "Default")
      (node (ref "J10") (pin "A31") (pinfunction "A31_A31") (pintype "passive"))
      (node (ref "J9") (pin "C31") (pinfunction "C31_C31") (pintype "passive"))
    )
    (net (code "156") (name "Net-(J10-PadC16)") (class "Default")
      (node (ref "J10") (pin "C16") (pinfunction "C16_C16") (pintype "passive"))
      (node (ref "J11") (pin "A16") (pinfunction "A16_A16") (pintype "passive"))
    )
    (net (code "157") (name "Net-(J10-PadC17)") (class "Default")
      (node (ref "J10") (pin "C17") (pinfunction "C17_C17") (pintype "passive"))
      (node (ref "J11") (pin "A17") (pinfunction "A17_A17") (pintype "passive"))
    )
    (net (code "158") (name "Net-(J10-PadC18)") (class "Default")
      (node (ref "J10") (pin "C18") (pinfunction "C18_C18") (pintype "passive"))
      (node (ref "J11") (pin "A18") (pinfunction "A18_A18") (pintype "passive"))
    )
    (net (code "159") (name "Net-(J10-PadC19)") (class "Default")
      (node (ref "J10") (pin "C19") (pinfunction "C19_C19") (pintype "passive"))
      (node (ref "J11") (pin "A19") (pinfunction "A19_A19") (pintype "passive"))
    )
    (net (code "160") (name "Net-(J10-PadC20)") (class "Default")
      (node (ref "J10") (pin "C20") (pinfunction "C20_C20") (pintype "passive"))
      (node (ref "J11") (pin "A20") (pinfunction "A20_A20") (pintype "passive"))
    )
    (net (code "161") (name "Net-(J10-PadC21)") (class "Default")
      (node (ref "J10") (pin "C21") (pinfunction "C21_C21") (pintype "passive"))
      (node (ref "J11") (pin "A21") (pinfunction "A21_A21") (pintype "passive"))
    )
    (net (code "162") (name "Net-(J10-PadC22)") (class "Default")
      (node (ref "J10") (pin "C22") (pinfunction "C22_C22") (pintype "passive"))
      (node (ref "J11") (pin "A22") (pinfunction "A22_A22") (pintype "passive"))
    )
    (net (code "163") (name "Net-(J10-PadC23)") (class "Default")
      (node (ref "J10") (pin "C23") (pinfunction "C23_C23") (pintype "passive"))
      (node (ref "J11") (pin "A23") (pinfunction "A23_A23") (pintype "passive"))
    )
    (net (code "164") (name "Net-(J10-PadC24)") (class "Default")
      (node (ref "J10") (pin "C24") (pinfunction "C24_C24") (pintype "passive"))
      (node (ref "J11") (pin "A24") (pinfunction "A24_A24") (pintype "passive"))
    )
    (net (code "165") (name "Net-(J10-PadC25)") (class "Default")
      (node (ref "J10") (pin "C25") (pinfunction "C25_C25") (pintype "passive"))
      (node (ref "J11") (pin "A25") (pinfunction "A25_A25") (pintype "passive"))
    )
    (net (code "166") (name "Net-(J10-PadC26)") (class "Default")
      (node (ref "J10") (pin "C26") (pinfunction "C26_C26") (pintype "passive"))
      (node (ref "J11") (pin "A26") (pinfunction "A26_A26") (pintype "passive"))
    )
    (net (code "167") (name "Net-(J10-PadC27)") (class "Default")
      (node (ref "J10") (pin "C27") (pinfunction "C27_C27") (pintype "passive"))
      (node (ref "J11") (pin "A27") (pinfunction "A27_A27") (pintype "passive"))
    )
    (net (code "168") (name "Net-(J10-PadC28)") (class "Default")
      (node (ref "J10") (pin "C28") (pinfunction "C28_C28") (pintype "passive"))
      (node (ref "J11") (pin "A28") (pinfunction "A28_A28") (pintype "passive"))
    )
    (net (code "169") (name "Net-(J10-PadC29)") (class "Default")
      (node (ref "J10") (pin "C29") (pinfunction "C29_C29") (pintype "passive"))
      (node (ref "J11") (pin "A29") (pinfunction "A29_A29") (pintype "passive"))
    )
    (net (code "170") (name "Net-(J10-PadC30)") (class "Default")
      (node (ref "J10") (pin "C30") (pinfunction "C30_C30") (pintype "passive"))
      (node (ref "J11") (pin "A30") (pinfunction "A30_A30") (pintype "passive"))
    )
    (net (code "171") (name "Net-(J10-PadC31)") (class "Default")
      (node (ref "J10") (pin "C31") (pinfunction "C31_C31") (pintype "passive"))
      (node (ref "J11") (pin "A31") (pinfunction "A31_A31") (pintype "passive"))
    )
    (net (code "172") (name "Net-(J11-PadC16)") (class "Default")
      (node (ref "J11") (pin "C16") (pinfunction "C16_C16") (pintype "passive"))
      (node (ref "J12") (pin "A16") (pinfunction "A16_A16") (pintype "passive"))
    )
    (net (code "173") (name "Net-(J11-PadC17)") (class "Default")
      (node (ref "J11") (pin "C17") (pinfunction "C17_C17") (pintype "passive"))
      (node (ref "J12") (pin "A17") (pinfunction "A17_A17") (pintype "passive"))
    )
    (net (code "174") (name "Net-(J11-PadC18)") (class "Default")
      (node (ref "J11") (pin "C18") (pinfunction "C18_C18") (pintype "passive"))
      (node (ref "J12") (pin "A18") (pinfunction "A18_A18") (pintype "passive"))
    )
    (net (code "175") (name "Net-(J11-PadC19)") (class "Default")
      (node (ref "J11") (pin "C19") (pinfunction "C19_C19") (pintype "passive"))
      (node (ref "J12") (pin "A19") (pinfunction "A19_A19") (pintype "passive"))
    )
    (net (code "176") (name "Net-(J11-PadC20)") (class "Default")
      (node (ref "J11") (pin "C20") (pinfunction "C20_C20") (pintype "passive"))
      (node (ref "J12") (pin "A20") (pinfunction "A20_A20") (pintype "passive"))
    )
    (net (code "177") (name "Net-(J11-PadC21)") (class "Default")
      (node (ref "J11") (pin "C21") (pinfunction "C21_C21") (pintype "passive"))
      (node (ref "J12") (pin "A21") (pinfunction "A21_A21") (pintype "passive"))
    )
    (net (code "178") (name "Net-(J11-PadC22)") (class "Default")
      (node (ref "J11") (pin "C22") (pinfunction "C22_C22") (pintype "passive"))
      (node (ref "J12") (pin "A22") (pinfunction "A22_A22") (pintype "passive"))
    )
    (net (code "179") (name "Net-(J11-PadC23)") (class "Default")
      (node (ref "J11") (pin "C23") (pinfunction "C23_C23") (pintype "passive"))
      (node (ref "J12") (pin "A23") (pinfunction "A23_A23") (pintype "passive"))
    )
    (net (code "180") (name "Net-(J11-PadC24)") (class "Default")
      (node (ref "J11") (pin "C24") (pinfunction "C24_C24") (pintype "passive"))
      (node (ref "J12") (pin "A24") (pinfunction "A24_A24") (pintype "passive"))
    )
    (net (code "181") (name "Net-(J11-PadC25)") (class "Default")
      (node (ref "J11") (pin "C25") (pinfunction "C25_C25") (pintype "passive"))
      (node (ref "J12") (pin "A25") (pinfunction "A25_A25") (pintype "passive"))
    )
    (net (code "182") (name "Net-(J11-PadC26)") (class "Default")
      (node (ref "J11") (pin "C26") (pinfunction "C26_C26") (pintype "passive"))
      (node (ref "J12") (pin "A26") (pinfunction "A26_A26") (pintype "passive"))
    )
    (net (code "183") (name "Net-(J11-PadC27)") (class "Default")
      (node (ref "J11") (pin "C27") (pinfunction "C27_C27") (pintype "passive"))
      (node (ref "J12") (pin "A27") (pinfunction "A27_A27") (pintype "passive"))
    )
    (net (code "184") (name "Net-(J11-PadC28)") (class "Default")
      (node (ref "J11") (pin "C28") (pinfunction "C28_C28") (pintype "passive"))
      (node (ref "J12") (pin "A28") (pinfunction "A28_A28") (pintype "passive"))
    )
    (net (code "185") (name "Net-(J11-PadC29)") (class "Default")
      (node (ref "J11") (pin "C29") (pinfunction "C29_C29") (pintype "passive"))
      (node (ref "J12") (pin "A29") (pinfunction "A29_A29") (pintype "passive"))
    )
    (net (code "186") (name "Net-(J11-PadC30)") (class "Default")
      (node (ref "J11") (pin "C30") (pinfunction "C30_C30") (pintype "passive"))
      (node (ref "J12") (pin "A30") (pinfunction "A30_A30") (pintype "passive"))
    )
    (net (code "187") (name "Net-(J11-PadC31)") (class "Default")
      (node (ref "J11") (pin "C31") (pinfunction "C31_C31") (pintype "passive"))
      (node (ref "J12") (pin "A31") (pinfunction "A31_A31") (pintype "passive"))
    )
    (net (code "188") (name "Net-(J12-PadC16)") (class "Default")
      (node (ref "J12") (pin "C16") (pinfunction "C16_C16") (pintype "passive"))
      (node (ref "J13") (pin "A16") (pinfunction "A16_A16") (pintype "passive"))
    )
    (net (code "189") (name "Net-(J12-PadC17)") (class "Default")
      (node (ref "J12") (pin "C17") (pinfunction "C17_C17") (pintype "passive"))
      (node (ref "J13") (pin "A17") (pinfunction "A17_A17") (pintype "passive"))
    )
    (net (code "190") (name "Net-(J12-PadC18)") (class "Default")
      (node (ref "J12") (pin "C18") (pinfunction "C18_C18") (pintype "passive"))
      (node (ref "J13") (pin "A18") (pinfunction "A18_A18") (pintype "passive"))
    )
    (net (code "191") (name "Net-(J12-PadC19)") (class "Default")
      (node (ref "J12") (pin "C19") (pinfunction "C19_C19") (pintype "passive"))
      (node (ref "J13") (pin "A19") (pinfunction "A19_A19") (pintype "passive"))
    )
    (net (code "192") (name "Net-(J12-PadC20)") (class "Default")
      (node (ref "J12") (pin "C20") (pinfunction "C20_C20") (pintype "passive"))
      (node (ref "J13") (pin "A20") (pinfunction "A20_A20") (pintype "passive"))
    )
    (net (code "193") (name "Net-(J12-PadC21)") (class "Default")
      (node (ref "J12") (pin "C21") (pinfunction "C21_C21") (pintype "passive"))
      (node (ref "J13") (pin "A21") (pinfunction "A21_A21") (pintype "passive"))
    )
    (net (code "194") (name "Net-(J12-PadC22)") (class "Default")
      (node (ref "J12") (pin "C22") (pinfunction "C22_C22") (pintype "passive"))
      (node (ref "J13") (pin "A22") (pinfunction "A22_A22") (pintype "passive"))
    )
    (net (code "195") (name "Net-(J12-PadC23)") (class "Default")
      (node (ref "J12") (pin "C23") (pinfunction "C23_C23") (pintype "passive"))
      (node (ref "J13") (pin "A23") (pinfunction "A23_A23") (pintype "passive"))
    )
    (net (code "196") (name "Net-(J12-PadC24)") (class "Default")
      (node (ref "J12") (pin "C24") (pinfunction "C24_C24") (pintype "passive"))
      (node (ref "J13") (pin "A24") (pinfunction "A24_A24") (pintype "passive"))
    )
    (net (code "197") (name "Net-(J12-PadC25)") (class "Default")
      (node (ref "J12") (pin "C25") (pinfunction "C25_C25") (pintype "passive"))
      (node (ref "J13") (pin "A25") (pinfunction "A25_A25") (pintype "passive"))
    )
    (net (code "198") (name "Net-(J12-PadC26)") (class "Default")
      (node (ref "J12") (pin "C26") (pinfunction "C26_C26") (pintype "passive"))
      (node (ref "J13") (pin "A26") (pinfunction "A26_A26") (pintype "passive"))
    )
    (net (code "199") (name "Net-(J12-PadC27)") (class "Default")
      (node (ref "J12") (pin "C27") (pinfunction "C27_C27") (pintype "passive"))
      (node (ref "J13") (pin "A27") (pinfunction "A27_A27") (pintype "passive"))
    )
    (net (code "200") (name "Net-(J12-PadC28)") (class "Default")
      (node (ref "J12") (pin "C28") (pinfunction "C28_C28") (pintype "passive"))
      (node (ref "J13") (pin "A28") (pinfunction "A28_A28") (pintype "passive"))
    )
    (net (code "201") (name "Net-(J12-PadC29)") (class "Default")
      (node (ref "J12") (pin "C29") (pinfunction "C29_C29") (pintype "passive"))
      (node (ref "J13") (pin "A29") (pinfunction "A29_A29") (pintype "passive"))
    )
    (net (code "202") (name "Net-(J12-PadC30)") (class "Default")
      (node (ref "J12") (pin "C30") (pinfunction "C30_C30") (pintype "passive"))
      (node (ref "J13") (pin "A30") (pinfunction "A30_A30") (pintype "passive"))
    )
    (net (code "203") (name "Net-(J12-PadC31)") (class "Default")
      (node (ref "J12") (pin "C31") (pinfunction "C31_C31") (pintype "passive"))
      (node (ref "J13") (pin "A31") (pinfunction "A31_A31") (pintype "passive"))
    )
    (net (code "204") (name "Net-(J13-PadC16)") (class "Default")
      (node (ref "J13") (pin "C16") (pinfunction "C16_C16") (pintype "passive"))
      (node (ref "J14") (pin "A16") (pinfunction "A16_A16") (pintype "passive"))
    )
    (net (code "205") (name "Net-(J13-PadC17)") (class "Default")
      (node (ref "J13") (pin "C17") (pinfunction "C17_C17") (pintype "passive"))
      (node (ref "J14") (pin "A17") (pinfunction "A17_A17") (pintype "passive"))
    )
    (net (code "206") (name "Net-(J13-PadC18)") (class "Default")
      (node (ref "J13") (pin "C18") (pinfunction "C18_C18") (pintype "passive"))
      (node (ref "J14") (pin "A18") (pinfunction "A18_A18") (pintype "passive"))
    )
    (net (code "207") (name "Net-(J13-PadC19)") (class "Default")
      (node (ref "J13") (pin "C19") (pinfunction "C19_C19") (pintype "passive"))
      (node (ref "J14") (pin "A19") (pinfunction "A19_A19") (pintype "passive"))
    )
    (net (code "208") (name "Net-(J13-PadC20)") (class "Default")
      (node (ref "J13") (pin "C20") (pinfunction "C20_C20") (pintype "passive"))
      (node (ref "J14") (pin "A20") (pinfunction "A20_A20") (pintype "passive"))
    )
    (net (code "209") (name "Net-(J13-PadC21)") (class "Default")
      (node (ref "J13") (pin "C21") (pinfunction "C21_C21") (pintype "passive"))
      (node (ref "J14") (pin "A21") (pinfunction "A21_A21") (pintype "passive"))
    )
    (net (code "210") (name "Net-(J13-PadC22)") (class "Default")
      (node (ref "J13") (pin "C22") (pinfunction "C22_C22") (pintype "passive"))
      (node (ref "J14") (pin "A22") (pinfunction "A22_A22") (pintype "passive"))
    )
    (net (code "211") (name "Net-(J13-PadC23)") (class "Default")
      (node (ref "J13") (pin "C23") (pinfunction "C23_C23") (pintype "passive"))
      (node (ref "J14") (pin "A23") (pinfunction "A23_A23") (pintype "passive"))
    )
    (net (code "212") (name "Net-(J13-PadC24)") (class "Default")
      (node (ref "J13") (pin "C24") (pinfunction "C24_C24") (pintype "passive"))
      (node (ref "J14") (pin "A24") (pinfunction "A24_A24") (pintype "passive"))
    )
    (net (code "213") (name "Net-(J13-PadC25)") (class "Default")
      (node (ref "J13") (pin "C25") (pinfunction "C25_C25") (pintype "passive"))
      (node (ref "J14") (pin "A25") (pinfunction "A25_A25") (pintype "passive"))
    )
    (net (code "214") (name "Net-(J13-PadC26)") (class "Default")
      (node (ref "J13") (pin "C26") (pinfunction "C26_C26") (pintype "passive"))
      (node (ref "J14") (pin "A26") (pinfunction "A26_A26") (pintype "passive"))
    )
    (net (code "215") (name "Net-(J13-PadC27)") (class "Default")
      (node (ref "J13") (pin "C27") (pinfunction "C27_C27") (pintype "passive"))
      (node (ref "J14") (pin "A27") (pinfunction "A27_A27") (pintype "passive"))
    )
    (net (code "216") (name "Net-(J13-PadC28)") (class "Default")
      (node (ref "J13") (pin "C28") (pinfunction "C28_C28") (pintype "passive"))
      (node (ref "J14") (pin "A28") (pinfunction "A28_A28") (pintype "passive"))
    )
    (net (code "217") (name "Net-(J13-PadC29)") (class "Default")
      (node (ref "J13") (pin "C29") (pinfunction "C29_C29") (pintype "passive"))
      (node (ref "J14") (pin "A29") (pinfunction "A29_A29") (pintype "passive"))
    )
    (net (code "218") (name "Net-(J13-PadC30)") (class "Default")
      (node (ref "J13") (pin "C30") (pinfunction "C30_C30") (pintype "passive"))
      (node (ref "J14") (pin "A30") (pinfunction "A30_A30") (pintype "passive"))
    )
    (net (code "219") (name "Net-(J13-PadC31)") (class "Default")
      (node (ref "J13") (pin "C31") (pinfunction "C31_C31") (pintype "passive"))
      (node (ref "J14") (pin "A31") (pinfunction "A31_A31") (pintype "passive"))
    )
    (net (code "220") (name "Net-(J14-PadC16)") (class "Default")
      (node (ref "J14") (pin "C16") (pinfunction "C16_C16") (pintype "passive"))
      (node (ref "J15") (pin "A16") (pinfunction "A16_A16") (pintype "passive"))
    )
    (net (code "221") (name "Net-(J14-PadC17)") (class "Default")
      (node (ref "J14") (pin "C17") (pinfunction "C17_C17") (pintype "passive"))
      (node (ref "J15") (pin "A17") (pinfunction "A17_A17") (pintype "passive"))
    )
    (net (code "222") (name "Net-(J14-PadC18)") (class "Default")
      (node (ref "J14") (pin "C18") (pinfunction "C18_C18") (pintype "passive"))
      (node (ref "J15") (pin "A18") (pinfunction "A18_A18") (pintype "passive"))
    )
    (net (code "223") (name "Net-(J14-PadC19)") (class "Default")
      (node (ref "J14") (pin "C19") (pinfunction "C19_C19") (pintype "passive"))
      (node (ref "J15") (pin "A19") (pinfunction "A19_A19") (pintype "passive"))
    )
    (net (code "224") (name "Net-(J14-PadC20)") (class "Default")
      (node (ref "J14") (pin "C20") (pinfunction "C20_C20") (pintype "passive"))
      (node (ref "J15") (pin "A20") (pinfunction "A20_A20") (pintype "passive"))
    )
    (net (code "225") (name "Net-(J14-PadC21)") (class "Default")
      (node (ref "J14") (pin "C21") (pinfunction "C21_C21") (pintype "passive"))
      (node (ref "J15") (pin "A21") (pinfunction "A21_A21") (pintype "passive"))
    )
    (net (code "226") (name "Net-(J14-PadC22)") (class "Default")
      (node (ref "J14") (pin "C22") (pinfunction "C22_C22") (pintype "passive"))
      (node (ref "J15") (pin "A22") (pinfunction "A22_A22") (pintype "passive"))
    )
    (net (code "227") (name "Net-(J14-PadC23)") (class "Default")
      (node (ref "J14") (pin "C23") (pinfunction "C23_C23") (pintype "passive"))
      (node (ref "J15") (pin "A23") (pinfunction "A23_A23") (pintype "passive"))
    )
    (net (code "228") (name "Net-(J14-PadC24)") (class "Default")
      (node (ref "J14") (pin "C24") (pinfunction "C24_C24") (pintype "passive"))
      (node (ref "J15") (pin "A24") (pinfunction "A24_A24") (pintype "passive"))
    )
    (net (code "229") (name "Net-(J14-PadC25)") (class "Default")
      (node (ref "J14") (pin "C25") (pinfunction "C25_C25") (pintype "passive"))
      (node (ref "J15") (pin "A25") (pinfunction "A25_A25") (pintype "passive"))
    )
    (net (code "230") (name "Net-(J14-PadC26)") (class "Default")
      (node (ref "J14") (pin "C26") (pinfunction "C26_C26") (pintype "passive"))
      (node (ref "J15") (pin "A26") (pinfunction "A26_A26") (pintype "passive"))
    )
    (net (code "231") (name "Net-(J14-PadC27)") (class "Default")
      (node (ref "J14") (pin "C27") (pinfunction "C27_C27") (pintype "passive"))
      (node (ref "J15") (pin "A27") (pinfunction "A27_A27") (pintype "passive"))
    )
    (net (code "232") (name "Net-(J14-PadC28)") (class "Default")
      (node (ref "J14") (pin "C28") (pinfunction "C28_C28") (pintype "passive"))
      (node (ref "J15") (pin "A28") (pinfunction "A28_A28") (pintype "passive"))
    )
    (net (code "233") (name "Net-(J14-PadC29)") (class "Default")
      (node (ref "J14") (pin "C29") (pinfunction "C29_C29") (pintype "passive"))
      (node (ref "J15") (pin "A29") (pinfunction "A29_A29") (pintype "passive"))
    )
    (net (code "234") (name "Net-(J14-PadC30)") (class "Default")
      (node (ref "J14") (pin "C30") (pinfunction "C30_C30") (pintype "passive"))
      (node (ref "J15") (pin "A30") (pinfunction "A30_A30") (pintype "passive"))
    )
    (net (code "235") (name "Net-(J14-PadC31)") (class "Default")
      (node (ref "J14") (pin "C31") (pinfunction "C31_C31") (pintype "passive"))
      (node (ref "J15") (pin "A31") (pinfunction "A31_A31") (pintype "passive"))
    )
    (net (code "236") (name "Net-(J15-PadC16)") (class "Default")
      (node (ref "J15") (pin "C16") (pinfunction "C16_C16") (pintype "passive"))
      (node (ref "J16") (pin "A16") (pinfunction "A16_A16") (pintype "passive"))
    )
    (net (code "237") (name "Net-(J15-PadC17)") (class "Default")
      (node (ref "J15") (pin "C17") (pinfunction "C17_C17") (pintype "passive"))
      (node (ref "J16") (pin "A17") (pinfunction "A17_A17") (pintype "passive"))
    )
    (net (code "238") (name "Net-(J15-PadC18)") (class "Default")
      (node (ref "J15") (pin "C18") (pinfunction "C18_C18") (pintype "passive"))
      (node (ref "J16") (pin "A18") (pinfunction "A18_A18") (pintype "passive"))
    )
    (net (code "239") (name "Net-(J15-PadC19)") (class "Default")
      (node (ref "J15") (pin "C19") (pinfunction "C19_C19") (pintype "passive"))
      (node (ref "J16") (pin "A19") (pinfunction "A19_A19") (pintype "passive"))
    )
    (net (code "240") (name "Net-(J15-PadC20)") (class "Default")
      (node (ref "J15") (pin "C20") (pinfunction "C20_C20") (pintype "passive"))
      (node (ref "J16") (pin "A20") (pinfunction "A20_A20") (pintype "passive"))
    )
    (net (code "241") (name "Net-(J15-PadC21)") (class "Default")
      (node (ref "J15") (pin "C21") (pinfunction "C21_C21") (pintype "passive"))
      (node (ref "J16") (pin "A21") (pinfunction "A21_A21") (pintype "passive"))
    )
    (net (code "242") (name "Net-(J15-PadC22)") (class "Default")
      (node (ref "J15") (pin "C22") (pinfunction "C22_C22") (pintype "passive"))
      (node (ref "J16") (pin "A22") (pinfunction "A22_A22") (pintype "passive"))
    )
    (net (code "243") (name "Net-(J15-PadC23)") (class "Default")
      (node (ref "J15") (pin "C23") (pinfunction "C23_C23") (pintype "passive"))
      (node (ref "J16") (pin "A23") (pinfunction "A23_A23") (pintype "passive"))
    )
    (net (code "244") (name "Net-(J15-PadC24)") (class "Default")
      (node (ref "J15") (pin "C24") (pinfunction "C24_C24") (pintype "passive"))
      (node (ref "J16") (pin "A24") (pinfunction "A24_A24") (pintype "passive"))
    )
    (net (code "245") (name "Net-(J15-PadC25)") (class "Default")
      (node (ref "J15") (pin "C25") (pinfunction "C25_C25") (pintype "passive"))
      (node (ref "J16") (pin "A25") (pinfunction "A25_A25") (pintype "passive"))
    )
    (net (code "246") (name "Net-(J15-PadC26)") (class "Default")
      (node (ref "J15") (pin "C26") (pinfunction "C26_C26") (pintype "passive"))
      (node (ref "J16") (pin "A26") (pinfunction "A26_A26") (pintype "passive"))
    )
    (net (code "247") (name "Net-(J15-PadC27)") (class "Default")
      (node (ref "J15") (pin "C27") (pinfunction "C27_C27") (pintype "passive"))
      (node (ref "J16") (pin "A27") (pinfunction "A27_A27") (pintype "passive"))
    )
    (net (code "248") (name "Net-(J15-PadC28)") (class "Default")
      (node (ref "J15") (pin "C28") (pinfunction "C28_C28") (pintype "passive"))
      (node (ref "J16") (pin "A28") (pinfunction "A28_A28") (pintype "passive"))
    )
    (net (code "249") (name "Net-(J15-PadC29)") (class "Default")
      (node (ref "J15") (pin "C29") (pinfunction "C29_C29") (pintype "passive"))
      (node (ref "J16") (pin "A29") (pinfunction "A29_A29") (pintype "passive"))
    )
    (net (code "250") (name "Net-(J15-PadC30)") (class "Default")
      (node (ref "J15") (pin "C30") (pinfunction "C30_C30") (pintype "passive"))
      (node (ref "J16") (pin "A30") (pinfunction "A30_A30") (pintype "passive"))
    )
    (net (code "251") (name "Net-(J15-PadC31)") (class "Default")
      (node (ref "J15") (pin "C31") (pinfunction "C31_C31") (pintype "passive"))
      (node (ref "J16") (pin "A31") (pinfunction "A31_A31") (pintype "passive"))
    )
    (net (code "252") (name "unconnected-(J16-PadC16)") (class "Default")
      (node (ref "J16") (pin "C16") (pinfunction "C16_C16") (pintype "passive"))
    )
    (net (code "253") (name "unconnected-(J16-PadC17)") (class "Default")
      (node (ref "J16") (pin "C17") (pinfunction "C17_C17") (pintype "passive"))
    )
    (net (code "254") (name "unconnected-(J16-PadC18)") (class "Default")
      (node (ref "J16") (pin "C18") (pinfunction "C18_C18") (pintype "passive"))
    )
    (net (code "255") (name "unconnected-(J16-PadC19)") (class "Default")
      (node (ref "J16") (pin "C19") (pinfunction "C19_C19") (pintype "passive"))
    )
    (net (code "256") (name "unconnected-(J16-PadC20)") (class "Default")
      (node (ref "J16") (pin "C20") (pinfunction "C20_C20") (pintype "passive"))
    )
    (net (code "257") (name "unconnected-(J16-PadC21)") (class "Default")
      (node (ref "J16") (pin "C21") (pinfunction "C21_C21") (pintype "passive"))
    )
    (net (code "258") (name "unconnected-(J16-PadC22)") (class "Default")
      (node (ref "J16") (pin "C22") (pinfunction "C22_C22") (pintype "passive"))
    )
    (net (code "259") (name "unconnected-(J16-PadC23)") (class "Default")
      (node (ref "J16") (pin "C23") (pinfunction "C23_C23") (pintype "passive"))
    )
    (net (code "260") (name "unconnected-(J16-PadC24)") (class "Default")
      (node (ref "J16") (pin "C24") (pinfunction "C24_C24") (pintype "passive"))
    )
    (net (code "261") (name "unconnected-(J16-PadC25)") (class "Default")
      (node (ref "J16") (pin "C25") (pinfunction "C25_C25") (pintype "passive"))
    )
    (net (code "262") (name "unconnected-(J16-PadC26)") (class "Default")
      (node (ref "J16") (pin "C26") (pinfunction "C26_C26") (pintype "passive"))
    )
    (net (code "263") (name "unconnected-(J16-PadC27)") (class "Default")
      (node (ref "J16") (pin "C27") (pinfunction "C27_C27") (pintype "passive"))
    )
    (net (code "264") (name "unconnected-(J16-PadC28)") (class "Default")
      (node (ref "J16") (pin "C28") (pinfunction "C28_C28") (pintype "passive"))
    )
    (net (code "265") (name "unconnected-(J16-PadC29)") (class "Default")
      (node (ref "J16") (pin "C29") (pinfunction "C29_C29") (pintype "passive"))
    )
    (net (code "266") (name "unconnected-(J16-PadC30)") (class "Default")
      (node (ref "J16") (pin "C30") (pinfunction "C30_C30") (pintype "passive"))
    )
    (net (code "267") (name "unconnected-(J16-PadC31)") (class "Default")
      (node (ref "J16") (pin "C31") (pinfunction "C31_C31") (pintype "passive"))
    )
  )
)
